# Speccy2007_128KY.net
KiCad netlist of a schematic drawn in EAGLE
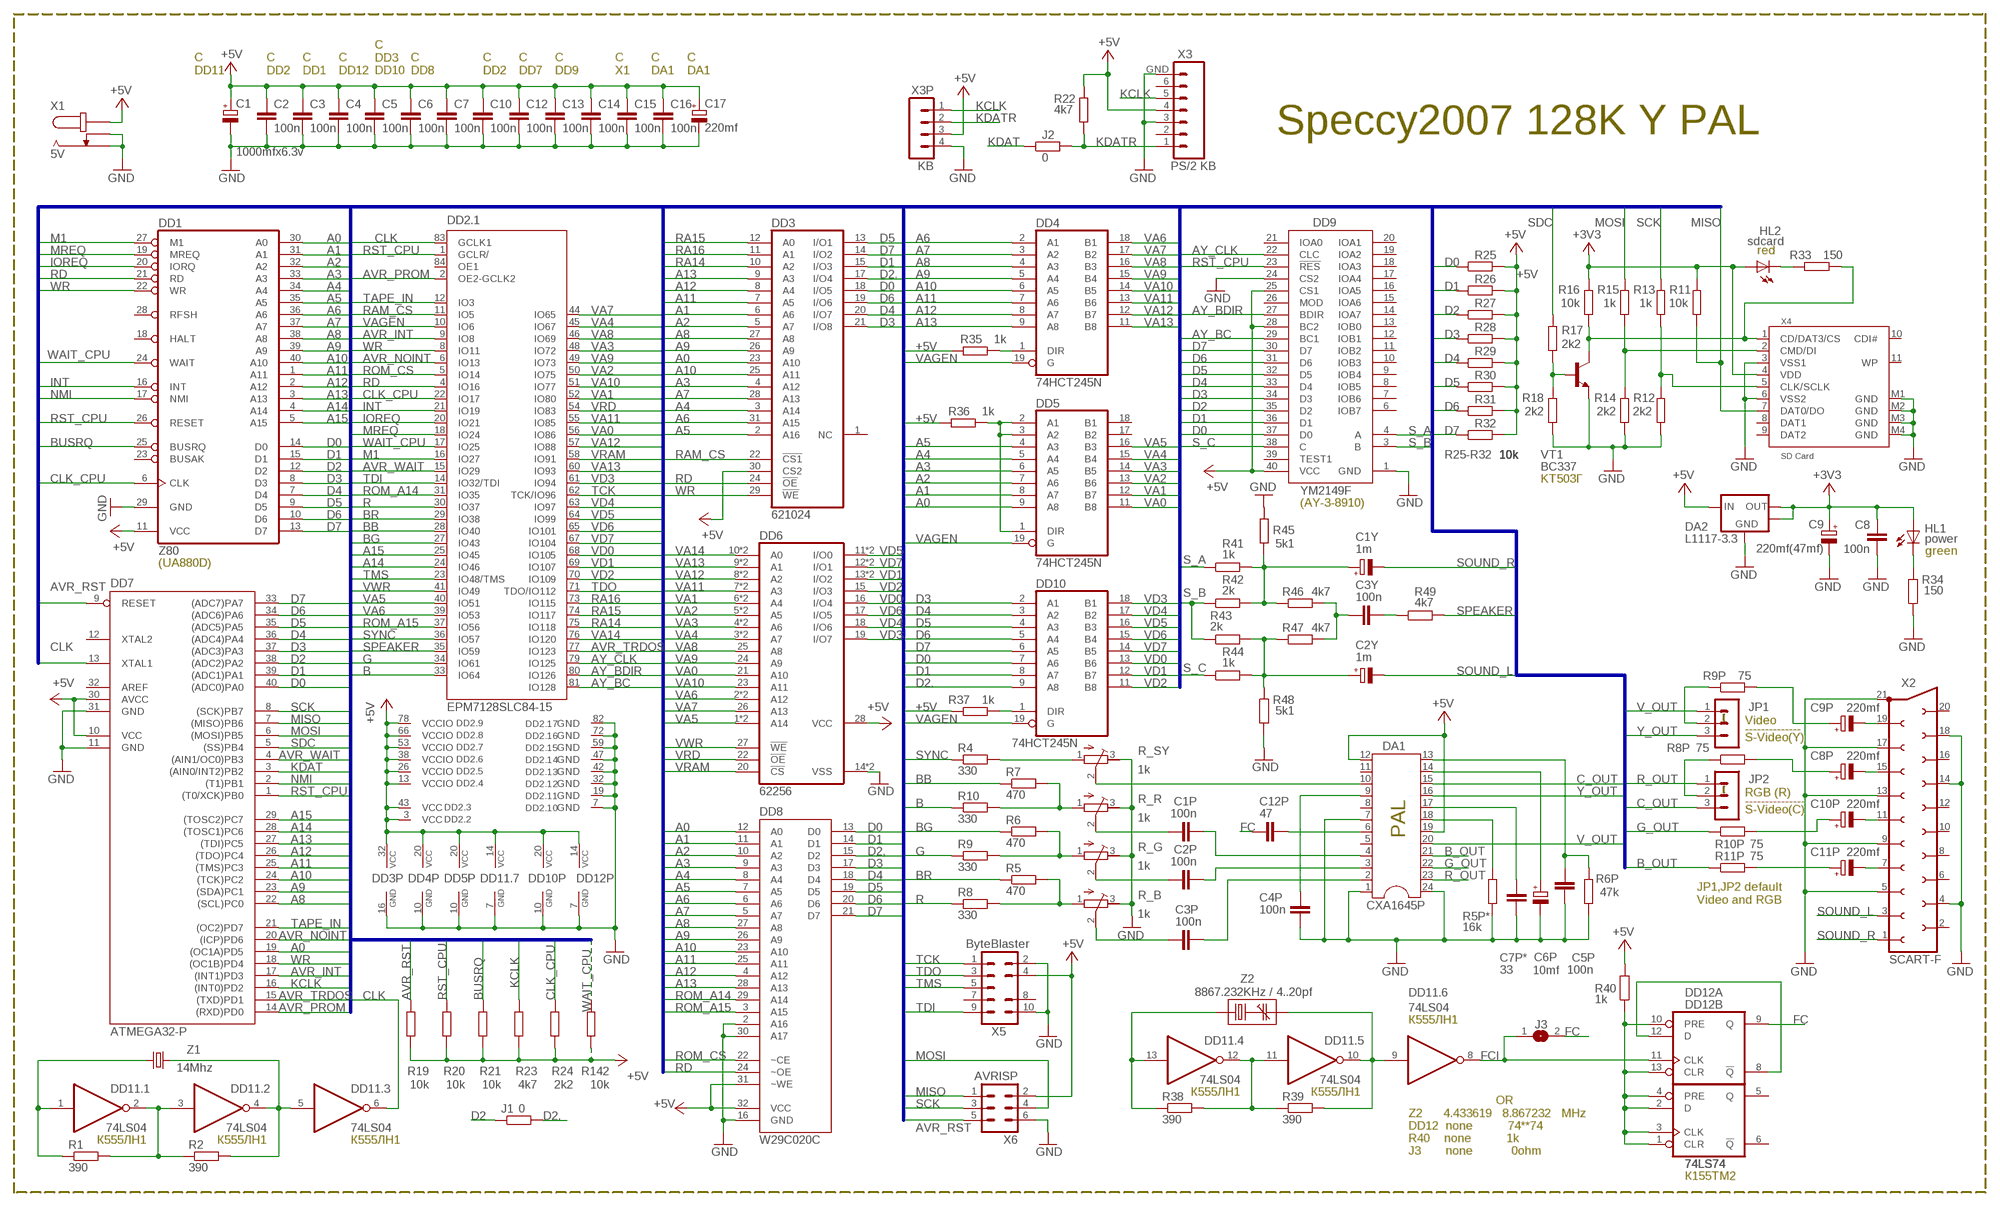
[diagram p0: schematic, sheet 1]

(export (version "E")
  (design (tool "Eeschema 10.0.6"))
  (components
    (comp (ref "C1")
      (value "1000mfx6.3v")
      (footprint "eagle-import:E3,5-8")
      (libsource (lib "eagle-import") (part "CPOL-EUE3.5-8"))
    )
    (comp (ref "C1P")
      (value "100n")
      (footprint "eagle-import:C0805")
      (libsource (lib "eagle-import") (part "C-EUC0805"))
    )
    (comp (ref "C1Y")
      (value "1m")
      (footprint "eagle-import:E2,5-5")
      (libsource (lib "eagle-import") (part "CPOL-EUE2.5-5"))
    )
    (comp (ref "C2")
      (value "100n")
      (footprint "eagle-import:C0805")
      (libsource (lib "eagle-import") (part "C-EUC0805"))
    )
    (comp (ref "C2P")
      (value "100n")
      (footprint "eagle-import:C0805")
      (libsource (lib "eagle-import") (part "C-EUC0805"))
    )
    (comp (ref "C2Y")
      (value "1m")
      (footprint "eagle-import:E2,5-5")
      (libsource (lib "eagle-import") (part "CPOL-EUE2.5-5"))
    )
    (comp (ref "C3")
      (value "100n")
      (footprint "eagle-import:C0805")
      (libsource (lib "eagle-import") (part "C-EUC0805"))
    )
    (comp (ref "C3P")
      (value "100n")
      (footprint "eagle-import:C0805")
      (libsource (lib "eagle-import") (part "C-EUC0805"))
    )
    (comp (ref "C3Y")
      (value "100n")
      (footprint "eagle-import:C0805")
      (libsource (lib "eagle-import") (part "C-EUC0805"))
    )
    (comp (ref "C4")
      (value "100n")
      (footprint "eagle-import:C1206")
      (libsource (lib "eagle-import") (part "C-EUC1206"))
    )
    (comp (ref "C4P")
      (value "100n")
      (footprint "eagle-import:C0805")
      (libsource (lib "eagle-import") (part "C-EUC0805"))
    )
    (comp (ref "C5")
      (value "100n")
      (footprint "eagle-import:C0805")
      (libsource (lib "eagle-import") (part "C-EUC0805"))
    )
    (comp (ref "C5P")
      (value "100n")
      (footprint "eagle-import:C1206")
      (libsource (lib "eagle-import") (part "C-EUC1206"))
    )
    (comp (ref "C6")
      (value "100n")
      (footprint "eagle-import:C1206")
      (libsource (lib "eagle-import") (part "C-EUC1206"))
    )
    (comp (ref "C6P")
      (value "10mf")
      (footprint "eagle-import:E2,5-5")
      (libsource (lib "eagle-import") (part "CPOL-EUE2.5-5"))
    )
    (comp (ref "C7")
      (value "100n")
      (footprint "eagle-import:C0805")
      (libsource (lib "eagle-import") (part "C-EUC0805"))
    )
    (comp (ref "C7P*")
      (value "33")
      (footprint "eagle-import:C1206")
      (libsource (lib "eagle-import") (part "C-EUC1206"))
    )
    (comp (ref "C8")
      (value "100n")
      (footprint "eagle-import:C0805")
      (libsource (lib "eagle-import") (part "C-EUC0805"))
    )
    (comp (ref "C8P")
      (value "220mf")
      (footprint "eagle-import:E2,5-6")
      (libsource (lib "eagle-import") (part "CPOL-EUE2.5-6"))
    )
    (comp (ref "C9")
      (value "220mf(47mf)")
      (footprint "eagle-import:E2,5-6")
      (libsource (lib "eagle-import") (part "CPOL-EUE2.5-6"))
    )
    (comp (ref "C9P")
      (value "220mf")
      (footprint "eagle-import:E2,5-6")
      (libsource (lib "eagle-import") (part "CPOL-EUE2.5-6"))
    )
    (comp (ref "C10")
      (value "100n")
      (footprint "eagle-import:C0805")
      (libsource (lib "eagle-import") (part "C-EUC0805"))
    )
    (comp (ref "C10P")
      (value "220mf")
      (footprint "eagle-import:E2,5-6")
      (libsource (lib "eagle-import") (part "CPOL-EUE2.5-6"))
    )
    (comp (ref "C11P")
      (value "220mf")
      (footprint "eagle-import:E2,5-6")
      (libsource (lib "eagle-import") (part "CPOL-EUE2.5-6"))
    )
    (comp (ref "C12")
      (value "100n")
      (footprint "eagle-import:C0805")
      (libsource (lib "eagle-import") (part "C-EUC0805"))
    )
    (comp (ref "C12P")
      (value "47")
      (footprint "eagle-import:C0805")
      (libsource (lib "eagle-import") (part "C-EUC0805"))
    )
    (comp (ref "C13")
      (value "100n")
      (footprint "eagle-import:C0805")
      (libsource (lib "eagle-import") (part "C-EUC0805"))
    )
    (comp (ref "C14")
      (value "100n")
      (footprint "eagle-import:C0805")
      (libsource (lib "eagle-import") (part "C-EUC0805"))
    )
    (comp (ref "C15")
      (value "100n")
      (footprint "eagle-import:C0805")
      (libsource (lib "eagle-import") (part "C-EUC0805"))
    )
    (comp (ref "C16")
      (value "100n")
      (footprint "eagle-import:C0805")
      (libsource (lib "eagle-import") (part "C-EUC0805"))
    )
    (comp (ref "C17")
      (value "220mf")
      (footprint "eagle-import:E2,5-6")
      (libsource (lib "eagle-import") (part "CPOL-EUE2.5-6"))
    )
    (comp (ref "DA1")
      (value "CXA1645P")
      (footprint "eagle-import:DIL24-4")
      (libsource (lib "eagle-import") (part "CXA1645-P"))
    )
    (comp (ref "DA2")
      (value "L1117-3.3")
      (footprint "eagle-import:SOT-223")
      (libsource (lib "eagle-import") (part "AP1117"))
    )
    (comp (ref "DD1")
      (value "Z80")
      (footprint "eagle-import:DIL40")
      (libsource (lib "eagle-import") (part "Z80CPU"))
    )
    (comp (ref "DD2")
      (value "EPM7128SLC84-15")
      (footprint "eagle-import:PGA-84-B")
      (libsource (lib "eagle-import") (part "EPM7128-J84"))
    )
    (comp (ref "DD3")
      (value "621024")
      (footprint "eagle-import:DIL32")
      (libsource (lib "eagle-import") (part "621024P"))
    )
    (comp (ref "DD4")
      (value "74HCT245N")
      (footprint "eagle-import:DIL20")
      (libsource (lib "eagle-import") (part "74245NHC"))
    )
    (comp (ref "DD5")
      (value "74HCT245N")
      (footprint "eagle-import:DIL20")
      (libsource (lib "eagle-import") (part "74245NHC"))
    )
    (comp (ref "DD6")
      (value "62256")
      (footprint "eagle-import:DIL28+6")
      (libsource (lib "eagle-import") (part "62256P+"))
    )
    (comp (ref "DD7")
      (value "ATMEGA32-P")
      (footprint "eagle-import:DIL40")
      (fields (field (name "MPN") "ATMEGA16-16PU"))
      (libsource (lib "eagle-import") (part "MEGA16-P"))
    )
    (comp (ref "DD8")
      (value "W29C020C")
      (footprint "eagle-import:DIL32")
      (libsource (lib "eagle-import") (part "W29C020C"))
    )
    (comp (ref "DD9")
      (value "YM2149F")
      (footprint "eagle-import:DIL40")
      (libsource (lib "eagle-import") (part "YM2149F"))
    )
    (comp (ref "DD10")
      (value "74HCT245N")
      (footprint "eagle-import:DIL20")
      (libsource (lib "eagle-import") (part "74245NHC"))
    )
    (comp (ref "DD11")
      (value "74LS04")
      (footprint "eagle-import:DIL14")
      (libsource (lib "eagle-import") (part "7404NLS"))
    )
    (comp (ref "DD12")
      (value "74LS74")
      (footprint "eagle-import:DIL14O")
      (libsource (lib "eagle-import") (part "7474OLS"))
    )
    (comp (ref "HL1")
      (value "power")
      (footprint "eagle-import:SML0805")
      (libsource (lib "eagle-import") (part "LEDSML0805"))
    )
    (comp (ref "HL2")
      (value "sdcard")
      (footprint "eagle-import:SML0805")
      (libsource (lib "eagle-import") (part "LEDSML0805"))
    )
    (comp (ref "J1")
      (value "0")
      (footprint "eagle-import:M1206")
      (libsource (lib "eagle-import") (part "rcl_R-EU_M1206"))
    )
    (comp (ref "J2")
      (value "0")
      (footprint "eagle-import:R1206")
      (libsource (lib "eagle-import") (part "rcl_R-EU_R1206"))
    )
    (comp (ref "J3") (value "SJ") (footprint "eagle-import:SJ") (libsource (lib "eagle-import") (part "SJ")))
    (comp (ref "JP1")
      (value "MA03-1")
      (footprint "eagle-import:MA03-1")
      (libsource (lib "eagle-import") (part "MA03-1"))
    )
    (comp (ref "JP2")
      (value "MA03-1")
      (footprint "eagle-import:MA03-1")
      (fields (field (name "OC_FARNELL") "unknown") (field (name "OC_NEWARK") "unknown"))
      (libsource (lib "eagle-import") (part "MA03-1"))
    )
    (comp (ref "R1")
      (value "390")
      (footprint "eagle-import:R0805")
      (libsource (lib "eagle-import") (part "rcl_R-EU_R0805"))
    )
    (comp (ref "R2")
      (value "390")
      (footprint "eagle-import:R0805")
      (libsource (lib "eagle-import") (part "rcl_R-EU_R0805"))
    )
    (comp (ref "R4")
      (value "330")
      (footprint "eagle-import:R0805")
      (libsource (lib "eagle-import") (part "rcl_R-EU_R0805"))
    )
    (comp (ref "R5")
      (value "470")
      (footprint "eagle-import:R0805")
      (libsource (lib "eagle-import") (part "rcl_R-EU_R0805"))
    )
    (comp (ref "R5P*")
      (value "16k")
      (footprint "eagle-import:M1206")
      (libsource (lib "eagle-import") (part "rcl_R-EU_M1206"))
    )
    (comp (ref "R6")
      (value "470")
      (footprint "eagle-import:R1206")
      (libsource (lib "eagle-import") (part "rcl_R-EU_R1206"))
    )
    (comp (ref "R6P")
      (value "47k")
      (footprint "eagle-import:R0805")
      (libsource (lib "eagle-import") (part "rcl_R-EU_R0805"))
    )
    (comp (ref "R7")
      (value "470")
      (footprint "eagle-import:0207_10")
      (libsource (lib "eagle-import") (part "R-EU_0207/10"))
    )
    (comp (ref "R8")
      (value "330")
      (footprint "eagle-import:R0805")
      (libsource (lib "eagle-import") (part "rcl_R-EU_R0805"))
    )
    (comp (ref "R8P")
      (value "75")
      (footprint "eagle-import:R1206")
      (libsource (lib "eagle-import") (part "rcl_R-EU_R1206"))
    )
    (comp (ref "R9")
      (value "330")
      (footprint "eagle-import:R0805")
      (libsource (lib "eagle-import") (part "rcl_R-EU_R0805"))
    )
    (comp (ref "R9P")
      (value "75")
      (footprint "eagle-import:R1206")
      (libsource (lib "eagle-import") (part "rcl_R-EU_R1206"))
    )
    (comp (ref "R10")
      (value "330")
      (footprint "eagle-import:R0805")
      (libsource (lib "eagle-import") (part "rcl_R-EU_R0805"))
    )
    (comp (ref "R10P")
      (value "75")
      (footprint "eagle-import:R1206")
      (libsource (lib "eagle-import") (part "rcl_R-EU_R1206"))
    )
    (comp (ref "R11")
      (value "10k")
      (footprint "eagle-import:R0805")
      (libsource (lib "eagle-import") (part "rcl_R-EU_R0805"))
    )
    (comp (ref "R11P")
      (value "75")
      (footprint "eagle-import:R1206")
      (libsource (lib "eagle-import") (part "rcl_R-EU_R1206"))
    )
    (comp (ref "R12")
      (value "2k2")
      (footprint "eagle-import:R1206")
      (libsource (lib "eagle-import") (part "rcl_R-EU_R1206"))
    )
    (comp (ref "R13")
      (value "1k")
      (footprint "eagle-import:R0805")
      (libsource (lib "eagle-import") (part "rcl_R-EU_R0805"))
    )
    (comp (ref "R14")
      (value "2k2")
      (footprint "eagle-import:R0805")
      (libsource (lib "eagle-import") (part "rcl_R-EU_R0805"))
    )
    (comp (ref "R15")
      (value "1k")
      (footprint "eagle-import:R0805")
      (libsource (lib "eagle-import") (part "rcl_R-EU_R0805"))
    )
    (comp (ref "R16")
      (value "10k")
      (footprint "eagle-import:R0805")
      (libsource (lib "eagle-import") (part "rcl_R-EU_R0805"))
    )
    (comp (ref "R17")
      (value "2k2")
      (footprint "eagle-import:R0805")
      (libsource (lib "eagle-import") (part "rcl_R-EU_R0805"))
    )
    (comp (ref "R18")
      (value "2k2")
      (footprint "eagle-import:R0805")
      (libsource (lib "eagle-import") (part "rcl_R-EU_R0805"))
    )
    (comp (ref "R19")
      (value "10k")
      (footprint "eagle-import:M0805")
      (libsource (lib "eagle-import") (part "rcl_R-EU_M0805"))
    )
    (comp (ref "R20")
      (value "10k")
      (footprint "eagle-import:R0805")
      (libsource (lib "eagle-import") (part "rcl_R-EU_R0805"))
    )
    (comp (ref "R21")
      (value "10k")
      (footprint "eagle-import:0207_10")
      (libsource (lib "eagle-import") (part "R-EU_0207/10"))
    )
    (comp (ref "R22")
      (value "4k7")
      (footprint "eagle-import:R0805")
      (libsource (lib "eagle-import") (part "rcl_R-EU_R0805"))
    )
    (comp (ref "R23")
      (value "4k7")
      (footprint "eagle-import:R1206")
      (libsource (lib "eagle-import") (part "rcl_R-EU_R1206"))
    )
    (comp (ref "R24")
      (value "2k2")
      (footprint "eagle-import:0207_10")
      (libsource (lib "eagle-import") (part "R-EU_0207/10"))
    )
    (comp (ref "R25")
      (value "10k")
      (footprint "eagle-import:R0805")
      (libsource (lib "eagle-import") (part "rcl_R-EU_R0805"))
    )
    (comp (ref "R26")
      (value "10k")
      (footprint "eagle-import:M0805")
      (libsource (lib "eagle-import") (part "rcl_R-EU_M0805"))
    )
    (comp (ref "R27")
      (value "10k")
      (footprint "eagle-import:R0805")
      (libsource (lib "eagle-import") (part "rcl_R-EU_R0805"))
    )
    (comp (ref "R28")
      (value "10k")
      (footprint "eagle-import:R0805")
      (libsource (lib "eagle-import") (part "rcl_R-EU_R0805"))
    )
    (comp (ref "R29")
      (value "10k")
      (footprint "eagle-import:R0805")
      (libsource (lib "eagle-import") (part "rcl_R-EU_R0805"))
    )
    (comp (ref "R30")
      (value "10k")
      (footprint "eagle-import:R0805")
      (libsource (lib "eagle-import") (part "rcl_R-EU_R0805"))
    )
    (comp (ref "R31")
      (value "10k")
      (footprint "eagle-import:R0805")
      (libsource (lib "eagle-import") (part "rcl_R-EU_R0805"))
    )
    (comp (ref "R32")
      (value "10k")
      (footprint "eagle-import:R0805")
      (libsource (lib "eagle-import") (part "rcl_R-EU_R0805"))
    )
    (comp (ref "R33")
      (value "150")
      (footprint "eagle-import:R1206")
      (libsource (lib "eagle-import") (part "rcl_R-EU_R1206"))
    )
    (comp (ref "R34")
      (value "150")
      (footprint "eagle-import:R0805")
      (libsource (lib "eagle-import") (part "rcl_R-EU_R0805"))
    )
    (comp (ref "R35")
      (value "1k")
      (footprint "eagle-import:R0805")
      (libsource (lib "eagle-import") (part "rcl_R-EU_R0805"))
    )
    (comp (ref "R36")
      (value "1k")
      (footprint "eagle-import:R0805")
      (libsource (lib "eagle-import") (part "rcl_R-EU_R0805"))
    )
    (comp (ref "R37")
      (value "1k")
      (footprint "eagle-import:R0805")
      (libsource (lib "eagle-import") (part "rcl_R-EU_R0805"))
    )
    (comp (ref "R38")
      (value "390")
      (footprint "eagle-import:R0805")
      (libsource (lib "eagle-import") (part "rcl_R-EU_R0805"))
    )
    (comp (ref "R39")
      (value "390")
      (footprint "eagle-import:R0805")
      (libsource (lib "eagle-import") (part "rcl_R-EU_R0805"))
    )
    (comp (ref "R40")
      (value "1k")
      (footprint "eagle-import:R0805")
      (libsource (lib "eagle-import") (part "rcl_R-EU_R0805"))
    )
    (comp (ref "R41")
      (value "1k")
      (footprint "eagle-import:R0805")
      (libsource (lib "eagle-import") (part "rcl_R-EU_R0805"))
    )
    (comp (ref "R42")
      (value "2k")
      (footprint "eagle-import:R0805")
      (libsource (lib "eagle-import") (part "rcl_R-EU_R0805"))
    )
    (comp (ref "R43")
      (value "2k")
      (footprint "eagle-import:R0805")
      (libsource (lib "eagle-import") (part "rcl_R-EU_R0805"))
    )
    (comp (ref "R44")
      (value "1k")
      (footprint "eagle-import:R1206")
      (libsource (lib "eagle-import") (part "rcl_R-EU_R1206"))
    )
    (comp (ref "R45")
      (value "5k1")
      (footprint "eagle-import:R1206")
      (libsource (lib "eagle-import") (part "rcl_R-EU_R1206"))
    )
    (comp (ref "R46")
      (value "4k7")
      (footprint "eagle-import:R1206")
      (libsource (lib "eagle-import") (part "rcl_R-EU_R1206"))
    )
    (comp (ref "R47")
      (value "4k7")
      (footprint "eagle-import:R0805")
      (libsource (lib "eagle-import") (part "rcl_R-EU_R0805"))
    )
    (comp (ref "R48")
      (value "5k1")
      (footprint "eagle-import:R0805")
      (libsource (lib "eagle-import") (part "rcl_R-EU_R0805"))
    )
    (comp (ref "R49")
      (value "4k7")
      (footprint "eagle-import:R0805")
      (libsource (lib "eagle-import") (part "rcl_R-EU_R0805"))
    )
    (comp (ref "R142")
      (value "10k")
      (footprint "eagle-import:0207_10")
      (libsource (lib "eagle-import") (part "R-EU_0207/10"))
    )
    (comp (ref "R_B")
      (value "1k")
      (footprint "eagle-import:RTRIM3296W")
      (libsource (lib "eagle-import") (part "R-TRIMM3296W"))
    )
    (comp (ref "R_G")
      (value "1k")
      (footprint "eagle-import:RTRIM3296W")
      (libsource (lib "eagle-import") (part "R-TRIMM3296W"))
    )
    (comp (ref "R_R")
      (value "1k")
      (footprint "eagle-import:RTRIM3296W")
      (libsource (lib "eagle-import") (part "R-TRIMM3296W"))
    )
    (comp (ref "R_SY")
      (value "1k")
      (footprint "eagle-import:RTRIM3296W")
      (libsource (lib "eagle-import") (part "R-TRIMM3296W"))
    )
    (comp (ref "VT1")
      (value "BC337")
      (footprint "eagle-import:TO92-CBE")
      (libsource (lib "eagle-import") (part "-NPN-TO92-CBEBC550"))
    )
    (comp (ref "X1")
      (value "5V")
      (footprint "eagle-import:POWER3.5")
      (libsource (lib "eagle-import") (part "POWER3.5"))
    )
    (comp (ref "X2")
      (value "SCART-F")
      (footprint "eagle-import:SCART-F")
      (libsource (lib "eagle-import") (part "SCART-F"))
    )
    (comp (ref "X3")
      (value "PS/2 KB")
      (footprint "eagle-import:MINI-DIN6")
      (libsource (lib "eagle-import") (part "MINI-DIN6PTH"))
    )
    (comp (ref "X3P")
      (value "KB")
      (footprint "eagle-import:MA04-1")
      (libsource (lib "eagle-import") (part "MA04-1"))
    )
    (comp (ref "X4")
      (value "SD Card")
      (footprint "eagle-import:SDCMF-10915W010")
      (libsource (lib "eagle-import") (part "SDCARD"))
    )
    (comp (ref "X5")
      (value "ByteBlaster")
      (footprint "eagle-import:MA05-2")
      (libsource (lib "eagle-import") (part "MA05-2"))
    )
    (comp (ref "X6")
      (value "AVRISP")
      (footprint "eagle-import:MA03-2")
      (libsource (lib "eagle-import") (part "MA03-2"))
    )
    (comp (ref "Z1")
      (value "14Mhz")
      (footprint "eagle-import:HC49U-H")
      (libsource (lib "eagle-import") (part "CRYSTALHC49U-H"))
    )
    (comp (ref "Z2")
      (value "8867.232KHz / 4..20pf")
      (footprint "eagle-import:HC49U-H")
      (libsource (lib "eagle-import") (part "ZC"))
    )
  )
  (nets
    (net (code "1") (name "+3V3") (class "Default")
      (node (ref "C8") (pin "1") (pinfunction "1_1") (pintype "passive"))
      (node (ref "C9") (pin "+") (pinfunction "+_+") (pintype "passive"))
      (node (ref "DA2") (pin "2") (pinfunction "OUT_2") (pintype "power_in"))
      (node (ref "DA2") (pin "4") (pinfunction "OUT'_4") (pintype "power_in"))
      (node (ref "HL1") (pin "A") (pinfunction "A_A") (pintype "passive"))
      (node (ref "HL2") (pin "A") (pinfunction "A_A") (pintype "passive"))
      (node (ref "R11") (pin "2") (pinfunction "2_2") (pintype "passive"))
      (node (ref "R16") (pin "2") (pinfunction "2_2") (pintype "passive"))
      (node (ref "X4") (pin "4") (pinfunction "VDD_4") (pintype "power_in"))
    )
    (net (code "2") (name "+5V") (class "Default")
      (node (ref "C1") (pin "+") (pinfunction "+_+") (pintype "passive"))
      (node (ref "C10") (pin "1") (pinfunction "1_1") (pintype "passive"))
      (node (ref "C12") (pin "1") (pinfunction "1_1") (pintype "passive"))
      (node (ref "C13") (pin "1") (pinfunction "1_1") (pintype "passive"))
      (node (ref "C14") (pin "1") (pinfunction "1_1") (pintype "passive"))
      (node (ref "C15") (pin "1") (pinfunction "1_1") (pintype "passive"))
      (node (ref "C16") (pin "1") (pinfunction "1_1") (pintype "passive"))
      (node (ref "C17") (pin "+") (pinfunction "+_+") (pintype "passive"))
      (node (ref "C2") (pin "1") (pinfunction "1_1") (pintype "passive"))
      (node (ref "C3") (pin "1") (pinfunction "1_1") (pintype "passive"))
      (node (ref "C4") (pin "1") (pinfunction "1_1") (pintype "passive"))
      (node (ref "C5") (pin "1") (pinfunction "1_1") (pintype "passive"))
      (node (ref "C6") (pin "1") (pinfunction "1_1") (pintype "passive"))
      (node (ref "C7") (pin "1") (pinfunction "1_1") (pintype "passive"))
      (node (ref "DA1") (pin "12") (pinfunction "12_12") (pintype "passive"))
      (node (ref "DA1") (pin "19") (pinfunction "19_19") (pintype "passive"))
      (node (ref "DA2") (pin "3") (pinfunction "IN_3") (pintype "power_in"))
      (node (ref "DD1") (pin "11") (pinfunction "VCC_11") (pintype "power_in"))
      (node (ref "DD10") (pin "20") (pinfunction "VCC_20") (pintype "power_in"))
      (node (ref "DD11") (pin "14") (pinfunction "VCC_14") (pintype "power_in"))
      (node (ref "DD12") (pin "14") (pinfunction "VCC_14") (pintype "power_in"))
      (node (ref "DD2") (pin "13") (pinfunction "VCCIO_13") (pintype "power_in"))
      (node (ref "DD2") (pin "26") (pinfunction "VCCIO_26") (pintype "power_in"))
      (node (ref "DD2") (pin "3") (pinfunction "VCC_3") (pintype "power_in"))
      (node (ref "DD2") (pin "38") (pinfunction "VCCIO_38") (pintype "power_in"))
      (node (ref "DD2") (pin "43") (pinfunction "VCC_43") (pintype "power_in"))
      (node (ref "DD2") (pin "53") (pinfunction "VCCIO_53") (pintype "power_in"))
      (node (ref "DD2") (pin "66") (pinfunction "VCCIO_66") (pintype "power_in"))
      (node (ref "DD2") (pin "78") (pinfunction "VCCIO_78") (pintype "power_in"))
      (node (ref "DD3") (pin "30") (pinfunction "CS2_30") (pintype "input"))
      (node (ref "DD3") (pin "32") (pinfunction "VCC_32") (pintype "power_in"))
      (node (ref "DD4") (pin "20") (pinfunction "VCC_20") (pintype "power_in"))
      (node (ref "DD5") (pin "20") (pinfunction "VCC_20") (pintype "power_in"))
      (node (ref "DD6") (pin "28") (pinfunction "VCC_28") (pintype "power_in"))
      (node (ref "DD7") (pin "10") (pinfunction "VCC_10") (pintype "power_in"))
      (node (ref "DD7") (pin "30") (pinfunction "AVCC_30") (pintype "power_in"))
      (node (ref "DD8") (pin "31") (pinfunction "~{WE}_31") (pintype "input"))
      (node (ref "DD8") (pin "32") (pinfunction "VCC_32") (pintype "power_in"))
      (node (ref "DD9") (pin "25") (pinfunction "CS1_25") (pintype "bidirectional"))
      (node (ref "DD9") (pin "28") (pinfunction "BC2_28") (pintype "bidirectional"))
      (node (ref "DD9") (pin "40") (pinfunction "VCC_40") (pintype "bidirectional"))
      (node (ref "R142") (pin "1") (pinfunction "1_1") (pintype "passive"))
      (node (ref "R19") (pin "1") (pinfunction "1_1") (pintype "passive"))
      (node (ref "R20") (pin "1") (pinfunction "1_1") (pintype "passive"))
      (node (ref "R21") (pin "1") (pinfunction "1_1") (pintype "passive"))
      (node (ref "R22") (pin "2") (pinfunction "2_2") (pintype "passive"))
      (node (ref "R23") (pin "1") (pinfunction "1_1") (pintype "passive"))
      (node (ref "R24") (pin "1") (pinfunction "1_1") (pintype "passive"))
      (node (ref "R25") (pin "2") (pinfunction "2_2") (pintype "passive"))
      (node (ref "R26") (pin "2") (pinfunction "2_2") (pintype "passive"))
      (node (ref "R27") (pin "2") (pinfunction "2_2") (pintype "passive"))
      (node (ref "R28") (pin "2") (pinfunction "2_2") (pintype "passive"))
      (node (ref "R29") (pin "2") (pinfunction "2_2") (pintype "passive"))
      (node (ref "R30") (pin "2") (pinfunction "2_2") (pintype "passive"))
      (node (ref "R31") (pin "2") (pinfunction "2_2") (pintype "passive"))
      (node (ref "R32") (pin "2") (pinfunction "2_2") (pintype "passive"))
      (node (ref "R35") (pin "2") (pinfunction "2_2") (pintype "passive"))
      (node (ref "R36") (pin "2") (pinfunction "2_2") (pintype "passive"))
      (node (ref "R37") (pin "2") (pinfunction "2_2") (pintype "passive"))
      (node (ref "R40") (pin "2") (pinfunction "2_2") (pintype "passive"))
      (node (ref "X1") (pin "P$1") (pinfunction "1_P$1") (pintype "passive"))
      (node (ref "X3") (pin "4") (pinfunction "4_4") (pintype "passive"))
      (node (ref "X3P") (pin "3") (pinfunction "3_3") (pintype "passive"))
      (node (ref "X5") (pin "4") (pinfunction "4_4") (pintype "passive"))
      (node (ref "X6") (pin "2") (pinfunction "2_2") (pintype "passive"))
    )
    (net (code "3") (name "/A0") (class "Default")
      (node (ref "DD1") (pin "30") (pinfunction "A0_30") (pintype "output"))
      (node (ref "DD3") (pin "23") (pinfunction "A10_23") (pintype "input"))
      (node (ref "DD5") (pin "9") (pinfunction "A8_9") (pintype "bidirectional"))
      (node (ref "DD7") (pin "19") (pinfunction "(OC1A)PD5_19") (pintype "bidirectional"))
      (node (ref "DD8") (pin "12") (pinfunction "A0_12") (pintype "input"))
    )
    (net (code "4") (name "/A1") (class "Default")
      (node (ref "DD1") (pin "31") (pinfunction "A1_31") (pintype "output"))
      (node (ref "DD3") (pin "6") (pinfunction "A6_6") (pintype "input"))
      (node (ref "DD5") (pin "8") (pinfunction "A7_8") (pintype "bidirectional"))
      (node (ref "DD8") (pin "11") (pinfunction "A1_11") (pintype "input"))
    )
    (net (code "5") (name "/A2") (class "Default")
      (node (ref "DD1") (pin "32") (pinfunction "A2_32") (pintype "output"))
      (node (ref "DD3") (pin "5") (pinfunction "A7_5") (pintype "input"))
      (node (ref "DD5") (pin "7") (pinfunction "A6_7") (pintype "bidirectional"))
      (node (ref "DD8") (pin "10") (pinfunction "A2_10") (pintype "input"))
    )
    (net (code "6") (name "/A3") (class "Default")
      (node (ref "DD1") (pin "33") (pinfunction "A3_33") (pintype "output"))
      (node (ref "DD3") (pin "4") (pinfunction "A12_4") (pintype "input"))
      (node (ref "DD5") (pin "6") (pinfunction "A5_6") (pintype "bidirectional"))
      (node (ref "DD8") (pin "9") (pinfunction "A3_9") (pintype "input"))
    )
    (net (code "7") (name "/A4") (class "Default")
      (node (ref "DD1") (pin "34") (pinfunction "A4_34") (pintype "output"))
      (node (ref "DD3") (pin "3") (pinfunction "A14_3") (pintype "input"))
      (node (ref "DD5") (pin "5") (pinfunction "A4_5") (pintype "bidirectional"))
      (node (ref "DD8") (pin "8") (pinfunction "A4_8") (pintype "input"))
    )
    (net (code "8") (name "/A5") (class "Default")
      (node (ref "DD1") (pin "35") (pinfunction "A5_35") (pintype "output"))
      (node (ref "DD3") (pin "2") (pinfunction "A16_2") (pintype "input"))
      (node (ref "DD5") (pin "4") (pinfunction "A3_4") (pintype "bidirectional"))
      (node (ref "DD8") (pin "7") (pinfunction "A5_7") (pintype "input"))
    )
    (net (code "9") (name "/A6") (class "Default")
      (node (ref "DD1") (pin "36") (pinfunction "A6_36") (pintype "output"))
      (node (ref "DD3") (pin "31") (pinfunction "A15_31") (pintype "input"))
      (node (ref "DD4") (pin "2") (pinfunction "A1_2") (pintype "bidirectional"))
      (node (ref "DD8") (pin "6") (pinfunction "A6_6") (pintype "input"))
    )
    (net (code "10") (name "/A7") (class "Default")
      (node (ref "DD1") (pin "37") (pinfunction "A7_37") (pintype "output"))
      (node (ref "DD3") (pin "28") (pinfunction "A13_28") (pintype "input"))
      (node (ref "DD4") (pin "3") (pinfunction "A2_3") (pintype "bidirectional"))
      (node (ref "DD8") (pin "5") (pinfunction "A7_5") (pintype "input"))
    )
    (net (code "11") (name "/A8") (class "Default")
      (node (ref "DD1") (pin "38") (pinfunction "A8_38") (pintype "output"))
      (node (ref "DD3") (pin "27") (pinfunction "A8_27") (pintype "input"))
      (node (ref "DD4") (pin "4") (pinfunction "A3_4") (pintype "bidirectional"))
      (node (ref "DD7") (pin "22") (pinfunction "(SCL)PC0_22") (pintype "bidirectional"))
      (node (ref "DD8") (pin "27") (pinfunction "A8_27") (pintype "input"))
    )
    (net (code "12") (name "/A9") (class "Default")
      (node (ref "DD1") (pin "39") (pinfunction "A9_39") (pintype "output"))
      (node (ref "DD3") (pin "26") (pinfunction "A9_26") (pintype "input"))
      (node (ref "DD4") (pin "5") (pinfunction "A4_5") (pintype "bidirectional"))
      (node (ref "DD7") (pin "23") (pinfunction "(SDA)PC1_23") (pintype "bidirectional"))
      (node (ref "DD8") (pin "26") (pinfunction "A9_26") (pintype "input"))
    )
    (net (code "13") (name "/A10") (class "Default")
      (node (ref "DD1") (pin "40") (pinfunction "A10_40") (pintype "output"))
      (node (ref "DD3") (pin "25") (pinfunction "A11_25") (pintype "input"))
      (node (ref "DD4") (pin "6") (pinfunction "A5_6") (pintype "bidirectional"))
      (node (ref "DD7") (pin "24") (pinfunction "(TCK)PC2_24") (pintype "bidirectional"))
      (node (ref "DD8") (pin "23") (pinfunction "A10_23") (pintype "input"))
    )
    (net (code "14") (name "/A11") (class "Default")
      (node (ref "DD1") (pin "1") (pinfunction "A11_1") (pintype "output"))
      (node (ref "DD3") (pin "7") (pinfunction "A5_7") (pintype "input"))
      (node (ref "DD4") (pin "7") (pinfunction "A6_7") (pintype "bidirectional"))
      (node (ref "DD7") (pin "25") (pinfunction "(TMS)PC3_25") (pintype "bidirectional"))
      (node (ref "DD8") (pin "25") (pinfunction "A11_25") (pintype "input"))
    )
    (net (code "15") (name "/A12") (class "Default")
      (node (ref "DD1") (pin "2") (pinfunction "A12_2") (pintype "output"))
      (node (ref "DD3") (pin "8") (pinfunction "A4_8") (pintype "input"))
      (node (ref "DD4") (pin "8") (pinfunction "A7_8") (pintype "bidirectional"))
      (node (ref "DD7") (pin "26") (pinfunction "(TDO)PC4_26") (pintype "bidirectional"))
      (node (ref "DD8") (pin "4") (pinfunction "A12_4") (pintype "input"))
    )
    (net (code "16") (name "/A13") (class "Default")
      (node (ref "DD1") (pin "3") (pinfunction "A13_3") (pintype "output"))
      (node (ref "DD3") (pin "9") (pinfunction "A3_9") (pintype "input"))
      (node (ref "DD4") (pin "9") (pinfunction "A8_9") (pintype "bidirectional"))
      (node (ref "DD7") (pin "27") (pinfunction "(TDI)PC5_27") (pintype "bidirectional"))
      (node (ref "DD8") (pin "28") (pinfunction "A13_28") (pintype "input"))
    )
    (net (code "17") (name "/A14") (class "Default")
      (node (ref "DD1") (pin "4") (pinfunction "A14_4") (pintype "output"))
      (node (ref "DD2") (pin "24") (pinfunction "IO46_24") (pintype "bidirectional"))
      (node (ref "DD7") (pin "28") (pinfunction "(TOSC1)PC6_28") (pintype "bidirectional"))
    )
    (net (code "18") (name "/A15") (class "Default")
      (node (ref "DD1") (pin "5") (pinfunction "A15_5") (pintype "output"))
      (node (ref "DD2") (pin "25") (pinfunction "IO45_25") (pintype "bidirectional"))
      (node (ref "DD7") (pin "29") (pinfunction "(TOSC2)PC7_29") (pintype "bidirectional"))
    )
    (net (code "19") (name "/AVR_INT") (class "Default")
      (node (ref "DD2") (pin "9") (pinfunction "IO8_9") (pintype "bidirectional"))
      (node (ref "DD7") (pin "17") (pinfunction "(INT1)PD3_17") (pintype "bidirectional"))
    )
    (net (code "20") (name "/AVR_NOINT") (class "Default")
      (node (ref "DD2") (pin "6") (pinfunction "IO13_6") (pintype "bidirectional"))
      (node (ref "DD7") (pin "20") (pinfunction "(ICP)PD6_20") (pintype "bidirectional"))
    )
    (net (code "21") (name "/AVR_PROM") (class "Default")
      (node (ref "DD2") (pin "2") (pinfunction "OE2-GCLK2_2") (pintype "input"))
      (node (ref "DD7") (pin "14") (pinfunction "(RXD)PD0_14") (pintype "bidirectional"))
    )
    (net (code "22") (name "/AVR_RST") (class "Default")
      (node (ref "DD7") (pin "9") (pinfunction "RESET_9") (pintype "input"))
      (node (ref "R19") (pin "2") (pinfunction "2_2") (pintype "passive"))
      (node (ref "X6") (pin "5") (pinfunction "5_5") (pintype "passive"))
    )
    (net (code "23") (name "/AVR_TRDOS") (class "Default")
      (node (ref "DD2") (pin "77") (pinfunction "IO123_77") (pintype "bidirectional"))
      (node (ref "DD7") (pin "15") (pinfunction "(TXD)PD1_15") (pintype "bidirectional"))
    )
    (net (code "24") (name "/AVR_WAIT") (class "Default")
      (node (ref "DD2") (pin "15") (pinfunction "IO29_15") (pintype "bidirectional"))
      (node (ref "DD7") (pin "4") (pinfunction "(AIN1/OC0)PB3_4") (pintype "bidirectional"))
    )
    (net (code "25") (name "/AY_BC") (class "Default")
      (node (ref "DD2") (pin "81") (pinfunction "IO128_81") (pintype "bidirectional"))
      (node (ref "DD9") (pin "29") (pinfunction "BC1_29") (pintype "bidirectional"))
    )
    (net (code "26") (name "/AY_BDIR") (class "Default")
      (node (ref "DD2") (pin "80") (pinfunction "IO126_80") (pintype "bidirectional"))
      (node (ref "DD9") (pin "27") (pinfunction "BDIR_27") (pintype "bidirectional"))
    )
    (net (code "27") (name "/AY_CLK") (class "Default")
      (node (ref "DD2") (pin "79") (pinfunction "IO125_79") (pintype "bidirectional"))
      (node (ref "DD9") (pin "22") (pinfunction "CLC_22") (pintype "bidirectional"))
    )
    (net (code "28") (name "/B") (class "Default")
      (node (ref "DD2") (pin "33") (pinfunction "IO64_33") (pintype "bidirectional"))
      (node (ref "R10") (pin "1") (pinfunction "1_1") (pintype "passive"))
    )
    (net (code "29") (name "/BB") (class "Default")
      (node (ref "DD2") (pin "28") (pinfunction "IO40_28") (pintype "bidirectional"))
      (node (ref "R7") (pin "1") (pinfunction "1_1") (pintype "passive"))
    )
    (net (code "30") (name "/BG") (class "Default")
      (node (ref "DD2") (pin "27") (pinfunction "IO43_27") (pintype "bidirectional"))
      (node (ref "R6") (pin "1") (pinfunction "1_1") (pintype "passive"))
    )
    (net (code "31") (name "/BR") (class "Default")
      (node (ref "DD2") (pin "29") (pinfunction "IO38_29") (pintype "bidirectional"))
      (node (ref "R5") (pin "1") (pinfunction "1_1") (pintype "passive"))
    )
    (net (code "32") (name "/BUSRQ") (class "Default")
      (node (ref "DD1") (pin "25") (pinfunction "BUSRQ_25") (pintype "input"))
      (node (ref "R21") (pin "2") (pinfunction "2_2") (pintype "passive"))
    )
    (net (code "33") (name "/B_OUT") (class "Default")
      (node (ref "DA1") (pin "21") (pinfunction "21_21") (pintype "passive"))
      (node (ref "R11P") (pin "1") (pinfunction "1_1") (pintype "passive"))
    )
    (net (code "34") (name "/CLK") (class "Default")
      (node (ref "DD11") (pin "6") (pinfunction "O_6") (pintype "output"))
      (node (ref "DD2") (pin "83") (pinfunction "GCLK1_83") (pintype "input"))
      (node (ref "DD7") (pin "13") (pinfunction "XTAL1_13") (pintype "bidirectional"))
    )
    (net (code "35") (name "/CLK_CPU") (class "Default")
      (node (ref "DD1") (pin "6") (pinfunction "CLK_6") (pintype "input"))
      (node (ref "DD2") (pin "22") (pinfunction "IO17_22") (pintype "bidirectional"))
      (node (ref "R24") (pin "2") (pinfunction "2_2") (pintype "passive"))
    )
    (net (code "36") (name "/C_OUT") (class "Default")
      (node (ref "DA1") (pin "15") (pinfunction "15_15") (pintype "passive"))
      (node (ref "JP2") (pin "3") (pinfunction "3_3") (pintype "passive"))
    )
    (net (code "37") (name "/D0") (class "Default")
      (node (ref "DD1") (pin "14") (pinfunction "D0_14") (pintype "bidirectional"))
      (node (ref "DD10") (pin "7") (pinfunction "A6_7") (pintype "bidirectional"))
      (node (ref "DD3") (pin "18") (pinfunction "I/O5_18") (pintype "bidirectional"))
      (node (ref "DD7") (pin "40") (pinfunction "(ADC0)PA0_40") (pintype "bidirectional"))
      (node (ref "DD8") (pin "13") (pinfunction "D0_13") (pintype "bidirectional"))
      (node (ref "DD9") (pin "37") (pinfunction "D0_37") (pintype "bidirectional"))
      (node (ref "R25") (pin "1") (pinfunction "1_1") (pintype "passive"))
    )
    (net (code "38") (name "/D1") (class "Default")
      (node (ref "DD1") (pin "15") (pinfunction "D1_15") (pintype "bidirectional"))
      (node (ref "DD10") (pin "8") (pinfunction "A7_8") (pintype "bidirectional"))
      (node (ref "DD3") (pin "15") (pinfunction "I/O3_15") (pintype "bidirectional"))
      (node (ref "DD7") (pin "39") (pinfunction "(ADC1)PA1_39") (pintype "bidirectional"))
      (node (ref "DD8") (pin "14") (pinfunction "D1_14") (pintype "bidirectional"))
      (node (ref "DD9") (pin "36") (pinfunction "D1_36") (pintype "bidirectional"))
      (node (ref "R26") (pin "1") (pinfunction "1_1") (pintype "passive"))
    )
    (net (code "39") (name "/D2") (class "Default")
      (node (ref "DD1") (pin "12") (pinfunction "D2_12") (pintype "bidirectional"))
      (node (ref "DD7") (pin "38") (pinfunction "(ADC2)PA2_38") (pintype "bidirectional"))
      (node (ref "DD9") (pin "35") (pinfunction "D2_35") (pintype "bidirectional"))
      (node (ref "J1") (pin "1") (pinfunction "1_1") (pintype "passive"))
      (node (ref "R27") (pin "1") (pinfunction "1_1") (pintype "passive"))
    )
    (net (code "40") (name "/D2.") (class "Default")
      (node (ref "DD10") (pin "9") (pinfunction "A8_9") (pintype "bidirectional"))
      (node (ref "DD3") (pin "17") (pinfunction "I/O4_17") (pintype "bidirectional"))
      (node (ref "DD8") (pin "15") (pinfunction "D2_15") (pintype "bidirectional"))
      (node (ref "J1") (pin "2") (pinfunction "2_2") (pintype "passive"))
    )
    (net (code "41") (name "/D3") (class "Default")
      (node (ref "DD1") (pin "8") (pinfunction "D3_8") (pintype "bidirectional"))
      (node (ref "DD10") (pin "2") (pinfunction "A1_2") (pintype "bidirectional"))
      (node (ref "DD3") (pin "21") (pinfunction "I/O8_21") (pintype "bidirectional"))
      (node (ref "DD7") (pin "37") (pinfunction "(ADC3)PA3_37") (pintype "bidirectional"))
      (node (ref "DD8") (pin "17") (pinfunction "D3_17") (pintype "bidirectional"))
      (node (ref "DD9") (pin "34") (pinfunction "D3_34") (pintype "bidirectional"))
      (node (ref "R28") (pin "1") (pinfunction "1_1") (pintype "passive"))
    )
    (net (code "42") (name "/D4") (class "Default")
      (node (ref "DD1") (pin "7") (pinfunction "D4_7") (pintype "bidirectional"))
      (node (ref "DD10") (pin "3") (pinfunction "A2_3") (pintype "bidirectional"))
      (node (ref "DD3") (pin "20") (pinfunction "I/O7_20") (pintype "bidirectional"))
      (node (ref "DD7") (pin "36") (pinfunction "(ADC4)PA4_36") (pintype "bidirectional"))
      (node (ref "DD8") (pin "18") (pinfunction "D4_18") (pintype "bidirectional"))
      (node (ref "DD9") (pin "33") (pinfunction "D4_33") (pintype "bidirectional"))
      (node (ref "R29") (pin "1") (pinfunction "1_1") (pintype "passive"))
    )
    (net (code "43") (name "/D5") (class "Default")
      (node (ref "DD1") (pin "9") (pinfunction "D5_9") (pintype "bidirectional"))
      (node (ref "DD10") (pin "4") (pinfunction "A3_4") (pintype "bidirectional"))
      (node (ref "DD3") (pin "13") (pinfunction "I/O1_13") (pintype "bidirectional"))
      (node (ref "DD7") (pin "35") (pinfunction "(ADC5)PA5_35") (pintype "bidirectional"))
      (node (ref "DD8") (pin "19") (pinfunction "D5_19") (pintype "bidirectional"))
      (node (ref "DD9") (pin "32") (pinfunction "D5_32") (pintype "bidirectional"))
      (node (ref "R30") (pin "1") (pinfunction "1_1") (pintype "passive"))
    )
    (net (code "44") (name "/D6") (class "Default")
      (node (ref "DD1") (pin "10") (pinfunction "D6_10") (pintype "bidirectional"))
      (node (ref "DD10") (pin "5") (pinfunction "A4_5") (pintype "bidirectional"))
      (node (ref "DD3") (pin "19") (pinfunction "I/O6_19") (pintype "bidirectional"))
      (node (ref "DD7") (pin "34") (pinfunction "(ADC6)PA6_34") (pintype "bidirectional"))
      (node (ref "DD8") (pin "20") (pinfunction "D6_20") (pintype "bidirectional"))
      (node (ref "DD9") (pin "31") (pinfunction "D6_31") (pintype "bidirectional"))
      (node (ref "R31") (pin "1") (pinfunction "1_1") (pintype "passive"))
    )
    (net (code "45") (name "/D7") (class "Default")
      (node (ref "DD1") (pin "13") (pinfunction "D7_13") (pintype "bidirectional"))
      (node (ref "DD10") (pin "6") (pinfunction "A5_6") (pintype "bidirectional"))
      (node (ref "DD3") (pin "14") (pinfunction "I/O2_14") (pintype "bidirectional"))
      (node (ref "DD7") (pin "33") (pinfunction "(ADC7)PA7_33") (pintype "bidirectional"))
      (node (ref "DD8") (pin "21") (pinfunction "D7_21") (pintype "bidirectional"))
      (node (ref "DD9") (pin "30") (pinfunction "D7_30") (pintype "bidirectional"))
      (node (ref "R32") (pin "1") (pinfunction "1_1") (pintype "passive"))
    )
    (net (code "46") (name "/FC") (class "Default")
      (node (ref "C12P") (pin "1") (pinfunction "1_1") (pintype "passive"))
      (node (ref "DD12") (pin "9") (pinfunction "Q_9") (pintype "output"))
      (node (ref "J3") (pin "2") (pinfunction "2_2") (pintype "passive"))
    )
    (net (code "47") (name "/FCI") (class "Default")
      (node (ref "DD11") (pin "8") (pinfunction "O_8") (pintype "output"))
      (node (ref "DD12") (pin "11") (pinfunction "CLK_11") (pintype "input"))
      (node (ref "J3") (pin "1") (pinfunction "1_1") (pintype "passive"))
    )
    (net (code "48") (name "/G") (class "Default")
      (node (ref "DD2") (pin "34") (pinfunction "IO61_34") (pintype "bidirectional"))
      (node (ref "R9") (pin "1") (pinfunction "1_1") (pintype "passive"))
    )
    (net (code "49") (name "/G_OUT") (class "Default")
      (node (ref "DA1") (pin "22") (pinfunction "22_22") (pintype "passive"))
      (node (ref "R10P") (pin "1") (pinfunction "1_1") (pintype "passive"))
    )
    (net (code "50") (name "/INT") (class "Default")
      (node (ref "DD1") (pin "16") (pinfunction "INT_16") (pintype "input"))
      (node (ref "DD2") (pin "21") (pinfunction "IO19_21") (pintype "bidirectional"))
    )
    (net (code "51") (name "/IOREQ") (class "Default")
      (node (ref "DD1") (pin "20") (pinfunction "IORQ_20") (pintype "output"))
      (node (ref "DD2") (pin "20") (pinfunction "IO21_20") (pintype "bidirectional"))
    )
    (net (code "52") (name "/KCLK") (class "Default")
      (node (ref "DD7") (pin "16") (pinfunction "(INT0)PD2_16") (pintype "bidirectional"))
      (node (ref "R23") (pin "2") (pinfunction "2_2") (pintype "passive"))
      (node (ref "X3") (pin "5") (pinfunction "5_5") (pintype "passive"))
      (node (ref "X3P") (pin "1") (pinfunction "1_1") (pintype "passive"))
    )
    (net (code "53") (name "/KDAT") (class "Default")
      (node (ref "DD7") (pin "3") (pinfunction "(AIN0/INT2)PB2_3") (pintype "bidirectional"))
      (node (ref "J2") (pin "1") (pinfunction "1_1") (pintype "passive"))
    )
    (net (code "54") (name "/KDATR") (class "Default")
      (node (ref "J2") (pin "2") (pinfunction "2_2") (pintype "passive"))
      (node (ref "R22") (pin "1") (pinfunction "1_1") (pintype "passive"))
      (node (ref "X3") (pin "1") (pinfunction "1_1") (pintype "passive"))
      (node (ref "X3P") (pin "2") (pinfunction "2_2") (pintype "passive"))
    )
    (net (code "55") (name "/M1") (class "Default")
      (node (ref "DD1") (pin "27") (pinfunction "M1_27") (pintype "output"))
      (node (ref "DD2") (pin "16") (pinfunction "IO27_16") (pintype "bidirectional"))
    )
    (net (code "56") (name "/MISO") (class "Default")
      (node (ref "DD7") (pin "7") (pinfunction "(MISO)PB6_7") (pintype "bidirectional"))
      (node (ref "R11") (pin "1") (pinfunction "1_1") (pintype "passive"))
      (node (ref "X4") (pin "7") (pinfunction "DAT0/DO_7") (pintype "bidirectional"))
      (node (ref "X6") (pin "1") (pinfunction "1_1") (pintype "passive"))
    )
    (net (code "57") (name "/MOSI") (class "Default")
      (node (ref "DD7") (pin "6") (pinfunction "(MOSI)PB5_6") (pintype "bidirectional"))
      (node (ref "R15") (pin "2") (pinfunction "2_2") (pintype "passive"))
      (node (ref "X6") (pin "4") (pinfunction "4_4") (pintype "passive"))
    )
    (net (code "58") (name "/MREQ") (class "Default")
      (node (ref "DD1") (pin "19") (pinfunction "MREQ_19") (pintype "output"))
      (node (ref "DD2") (pin "18") (pinfunction "IO24_18") (pintype "bidirectional"))
    )
    (net (code "59") (name "/NMI") (class "Default")
      (node (ref "DD1") (pin "17") (pinfunction "NMI_17") (pintype "input"))
      (node (ref "DD7") (pin "2") (pinfunction "(T1)PB1_2") (pintype "bidirectional"))
    )
    (net (code "60") (name "/R") (class "Default")
      (node (ref "DD2") (pin "30") (pinfunction "IO37_30") (pintype "bidirectional"))
      (node (ref "R8") (pin "1") (pinfunction "1_1") (pintype "passive"))
    )
    (net (code "61") (name "/RA14") (class "Default")
      (node (ref "DD2") (pin "75") (pinfunction "IO118_75") (pintype "bidirectional"))
      (node (ref "DD3") (pin "10") (pinfunction "A2_10") (pintype "input"))
    )
    (net (code "62") (name "/RA15") (class "Default")
      (node (ref "DD2") (pin "74") (pinfunction "IO117_74") (pintype "bidirectional"))
      (node (ref "DD3") (pin "12") (pinfunction "A0_12") (pintype "input"))
    )
    (net (code "63") (name "/RA16") (class "Default")
      (node (ref "DD2") (pin "73") (pinfunction "IO115_73") (pintype "bidirectional"))
      (node (ref "DD3") (pin "11") (pinfunction "A1_11") (pintype "input"))
    )
    (net (code "64") (name "/RAM_CS") (class "Default")
      (node (ref "DD2") (pin "11") (pinfunction "IO5_11") (pintype "bidirectional"))
      (node (ref "DD3") (pin "22") (pinfunction "~{CS1}_22") (pintype "input"))
    )
    (net (code "65") (name "/RD") (class "Default")
      (node (ref "DD1") (pin "21") (pinfunction "RD_21") (pintype "output"))
      (node (ref "DD2") (pin "4") (pinfunction "IO16_4") (pintype "bidirectional"))
      (node (ref "DD3") (pin "24") (pinfunction "~{OE}_24") (pintype "input"))
      (node (ref "DD8") (pin "24") (pinfunction "~{OE}_24") (pintype "input"))
    )
    (net (code "66") (name "/ROM_A14") (class "Default")
      (node (ref "DD2") (pin "31") (pinfunction "IO35_31") (pintype "bidirectional"))
      (node (ref "DD8") (pin "29") (pinfunction "A14_29") (pintype "input"))
    )
    (net (code "67") (name "/ROM_A15") (class "Default")
      (node (ref "DD2") (pin "37") (pinfunction "IO56_37") (pintype "bidirectional"))
      (node (ref "DD8") (pin "3") (pinfunction "A15_3") (pintype "input"))
    )
    (net (code "68") (name "/ROM_CS") (class "Default")
      (node (ref "DD2") (pin "5") (pinfunction "IO14_5") (pintype "bidirectional"))
      (node (ref "DD8") (pin "22") (pinfunction "~{CE}_22") (pintype "input"))
    )
    (net (code "69") (name "/RST_CPU") (class "Default")
      (node (ref "DD1") (pin "26") (pinfunction "RESET_26") (pintype "input"))
      (node (ref "DD2") (pin "1") (pinfunction "GCLR/_1") (pintype "input"))
      (node (ref "DD7") (pin "1") (pinfunction "(T0/XCK)PB0_1") (pintype "bidirectional"))
      (node (ref "DD9") (pin "23") (pinfunction "~{RES}_23") (pintype "bidirectional"))
      (node (ref "R20") (pin "2") (pinfunction "2_2") (pintype "passive"))
    )
    (net (code "70") (name "/R_OUT") (class "Default")
      (node (ref "DA1") (pin "23") (pinfunction "23_23") (pintype "passive"))
      (node (ref "JP2") (pin "1") (pinfunction "1_1") (pintype "passive"))
    )
    (net (code "71") (name "/SCK") (class "Default")
      (node (ref "DD7") (pin "8") (pinfunction "(SCK)PB7_8") (pintype "bidirectional"))
      (node (ref "R13") (pin "2") (pinfunction "2_2") (pintype "passive"))
      (node (ref "X6") (pin "3") (pinfunction "3_3") (pintype "passive"))
    )
    (net (code "72") (name "/SDC") (class "Default")
      (node (ref "DD7") (pin "5") (pinfunction "(SS)PB4_5") (pintype "bidirectional"))
      (node (ref "R17") (pin "2") (pinfunction "2_2") (pintype "passive"))
    )
    (net (code "73") (name "/SOUND_L") (class "Default")
      (node (ref "C2Y") (pin "-") (pinfunction "-_-") (pintype "passive"))
      (node (ref "X2") (pin "3") (pinfunction "3_3") (pintype "passive"))
    )
    (net (code "74") (name "/SOUND_R") (class "Default")
      (node (ref "C1Y") (pin "-") (pinfunction "-_-") (pintype "passive"))
      (node (ref "X2") (pin "1") (pinfunction "1_1") (pintype "passive"))
    )
    (net (code "75") (name "/SPEAKER") (class "Default")
      (node (ref "DD2") (pin "35") (pinfunction "IO59_35") (pintype "bidirectional"))
      (node (ref "R49") (pin "2") (pinfunction "2_2") (pintype "passive"))
    )
    (net (code "76") (name "/SYNC") (class "Default")
      (node (ref "DD2") (pin "36") (pinfunction "IO57_36") (pintype "bidirectional"))
      (node (ref "R4") (pin "1") (pinfunction "1_1") (pintype "passive"))
    )
    (net (code "77") (name "/S_A") (class "Default")
      (node (ref "DD9") (pin "4") (pinfunction "A_4") (pintype "bidirectional"))
      (node (ref "R41") (pin "1") (pinfunction "1_1") (pintype "passive"))
    )
    (net (code "78") (name "/S_B") (class "Default")
      (node (ref "DD9") (pin "3") (pinfunction "B_3") (pintype "bidirectional"))
      (node (ref "R42") (pin "1") (pinfunction "1_1") (pintype "passive"))
      (node (ref "R43") (pin "1") (pinfunction "1_1") (pintype "passive"))
    )
    (net (code "79") (name "/S_C") (class "Default")
      (node (ref "DD9") (pin "38") (pinfunction "C_38") (pintype "bidirectional"))
      (node (ref "R44") (pin "1") (pinfunction "1_1") (pintype "passive"))
    )
    (net (code "80") (name "/TAPE_IN") (class "Default")
      (node (ref "DD2") (pin "12") (pinfunction "IO3_12") (pintype "bidirectional"))
      (node (ref "DD7") (pin "21") (pinfunction "(OC2)PD7_21") (pintype "bidirectional"))
    )
    (net (code "81") (name "/TCK") (class "Default")
      (node (ref "DD2") (pin "62") (pinfunction "TCK/IO96_62") (pintype "bidirectional"))
      (node (ref "X5") (pin "1") (pinfunction "1_1") (pintype "passive"))
    )
    (net (code "82") (name "/TDI") (class "Default")
      (node (ref "DD2") (pin "14") (pinfunction "IO32/TDI_14") (pintype "bidirectional"))
      (node (ref "X5") (pin "9") (pinfunction "9_9") (pintype "passive"))
    )
    (net (code "83") (name "/TDO") (class "Default")
      (node (ref "DD2") (pin "71") (pinfunction "TDO/IO112_71") (pintype "bidirectional"))
      (node (ref "X5") (pin "3") (pinfunction "3_3") (pintype "passive"))
    )
    (net (code "84") (name "/TMS") (class "Default")
      (node (ref "DD2") (pin "23") (pinfunction "IO48/TMS_23") (pintype "bidirectional"))
      (node (ref "X5") (pin "5") (pinfunction "5_5") (pintype "passive"))
    )
    (net (code "85") (name "/VA0") (class "Default")
      (node (ref "DD2") (pin "56") (pinfunction "IO86_56") (pintype "bidirectional"))
      (node (ref "DD5") (pin "11") (pinfunction "B8_11") (pintype "bidirectional"))
      (node (ref "DD6") (pin "21") (pinfunction "A10_21") (pintype "input"))
    )
    (net (code "86") (name "/VA1") (class "Default")
      (node (ref "DD2") (pin "52") (pinfunction "IO80_52") (pintype "bidirectional"))
      (node (ref "DD5") (pin "12") (pinfunction "B7_12") (pintype "bidirectional"))
      (node (ref "DD6") (pin "6") (pinfunction "A4_6") (pintype "input"))
      (node (ref "DD6") (pin "P$6") (pinfunction "A4_P$6") (pintype "input"))
    )
    (net (code "87") (name "/VA2") (class "Default")
      (node (ref "DD2") (pin "50") (pinfunction "IO75_50") (pintype "bidirectional"))
      (node (ref "DD5") (pin "13") (pinfunction "B6_13") (pintype "bidirectional"))
      (node (ref "DD6") (pin "5") (pinfunction "A5_5") (pintype "input"))
      (node (ref "DD6") (pin "P$5") (pinfunction "A5_P$5") (pintype "input"))
    )
    (net (code "88") (name "/VA3") (class "Default")
      (node (ref "DD2") (pin "48") (pinfunction "IO72_48") (pintype "bidirectional"))
      (node (ref "DD5") (pin "14") (pinfunction "B5_14") (pintype "bidirectional"))
      (node (ref "DD6") (pin "4") (pinfunction "A6_4") (pintype "input"))
      (node (ref "DD6") (pin "P$4") (pinfunction "A6_P$4") (pintype "input"))
    )
    (net (code "89") (name "/VA4") (class "Default")
      (node (ref "DD2") (pin "45") (pinfunction "IO67_45") (pintype "bidirectional"))
      (node (ref "DD5") (pin "15") (pinfunction "B4_15") (pintype "bidirectional"))
      (node (ref "DD6") (pin "3") (pinfunction "A7_3") (pintype "input"))
      (node (ref "DD6") (pin "P$3") (pinfunction "A7_P$3") (pintype "input"))
    )
    (net (code "90") (name "/VA5") (class "Default")
      (node (ref "DD2") (pin "40") (pinfunction "IO51_40") (pintype "bidirectional"))
      (node (ref "DD5") (pin "16") (pinfunction "B3_16") (pintype "bidirectional"))
      (node (ref "DD6") (pin "1") (pinfunction "A14_1") (pintype "input"))
      (node (ref "DD6") (pin "P$1") (pinfunction "A14_P$1") (pintype "input"))
    )
    (net (code "91") (name "/VA6") (class "Default")
      (node (ref "DD2") (pin "39") (pinfunction "IO53_39") (pintype "bidirectional"))
      (node (ref "DD4") (pin "18") (pinfunction "B1_18") (pintype "bidirectional"))
      (node (ref "DD6") (pin "2") (pinfunction "A12_2") (pintype "input"))
      (node (ref "DD6") (pin "P$2") (pinfunction "A12_P$2") (pintype "input"))
    )
    (net (code "92") (name "/VA7") (class "Default")
      (node (ref "DD2") (pin "44") (pinfunction "IO65_44") (pintype "bidirectional"))
      (node (ref "DD4") (pin "17") (pinfunction "B2_17") (pintype "bidirectional"))
      (node (ref "DD6") (pin "26") (pinfunction "A13_26") (pintype "input"))
    )
    (net (code "93") (name "/VA8") (class "Default")
      (node (ref "DD2") (pin "46") (pinfunction "IO69_46") (pintype "bidirectional"))
      (node (ref "DD4") (pin "16") (pinfunction "B3_16") (pintype "bidirectional"))
      (node (ref "DD6") (pin "25") (pinfunction "A8_25") (pintype "input"))
    )
    (net (code "94") (name "/VA9") (class "Default")
      (node (ref "DD2") (pin "49") (pinfunction "IO73_49") (pintype "bidirectional"))
      (node (ref "DD4") (pin "15") (pinfunction "B4_15") (pintype "bidirectional"))
      (node (ref "DD6") (pin "24") (pinfunction "A9_24") (pintype "input"))
    )
    (net (code "95") (name "/VA10") (class "Default")
      (node (ref "DD2") (pin "51") (pinfunction "IO77_51") (pintype "bidirectional"))
      (node (ref "DD4") (pin "14") (pinfunction "B5_14") (pintype "bidirectional"))
      (node (ref "DD6") (pin "23") (pinfunction "A11_23") (pintype "input"))
    )
    (net (code "96") (name "/VA11") (class "Default")
      (node (ref "DD2") (pin "55") (pinfunction "IO85_55") (pintype "bidirectional"))
      (node (ref "DD4") (pin "13") (pinfunction "B6_13") (pintype "bidirectional"))
      (node (ref "DD6") (pin "7") (pinfunction "A3_7") (pintype "input"))
      (node (ref "DD6") (pin "P$7") (pinfunction "A3_P$7") (pintype "input"))
    )
    (net (code "97") (name "/VA12") (class "Default")
      (node (ref "DD2") (pin "57") (pinfunction "IO88_57") (pintype "bidirectional"))
      (node (ref "DD4") (pin "12") (pinfunction "B7_12") (pintype "bidirectional"))
      (node (ref "DD6") (pin "8") (pinfunction "A2_8") (pintype "input"))
      (node (ref "DD6") (pin "P$8") (pinfunction "A2_P$8") (pintype "input"))
    )
    (net (code "98") (name "/VA13") (class "Default")
      (node (ref "DD2") (pin "60") (pinfunction "IO93_60") (pintype "bidirectional"))
      (node (ref "DD4") (pin "11") (pinfunction "B8_11") (pintype "bidirectional"))
      (node (ref "DD6") (pin "9") (pinfunction "A1_9") (pintype "input"))
      (node (ref "DD6") (pin "P$9") (pinfunction "A1_P$9") (pintype "input"))
    )
    (net (code "99") (name "/VA14") (class "Default")
      (node (ref "DD2") (pin "76") (pinfunction "IO120_76") (pintype "bidirectional"))
      (node (ref "DD6") (pin "10") (pinfunction "A0_10") (pintype "input"))
      (node (ref "DD6") (pin "P$10") (pinfunction "A0_P$10") (pintype "input"))
    )
    (net (code "100") (name "/VAGEN") (class "Default")
      (node (ref "DD10") (pin "19") (pinfunction "G_19") (pintype "input"))
      (node (ref "DD2") (pin "10") (pinfunction "IO6_10") (pintype "bidirectional"))
      (node (ref "DD4") (pin "19") (pinfunction "G_19") (pintype "input"))
      (node (ref "DD5") (pin "19") (pinfunction "G_19") (pintype "input"))
    )
    (net (code "101") (name "/VD0") (class "Default")
      (node (ref "DD10") (pin "13") (pinfunction "B6_13") (pintype "bidirectional"))
      (node (ref "DD2") (pin "68") (pinfunction "IO105_68") (pintype "bidirectional"))
      (node (ref "DD6") (pin "16") (pinfunction "I/O4_16") (pintype "bidirectional"))
    )
    (net (code "102") (name "/VD1") (class "Default")
      (node (ref "DD10") (pin "12") (pinfunction "B7_12") (pintype "bidirectional"))
      (node (ref "DD2") (pin "69") (pinfunction "IO107_69") (pintype "bidirectional"))
      (node (ref "DD6") (pin "13") (pinfunction "I/O2_13") (pintype "bidirectional"))
      (node (ref "DD6") (pin "P$13") (pinfunction "I/O2_P$13") (pintype "bidirectional"))
    )
    (net (code "103") (name "/VD2") (class "Default")
      (node (ref "DD10") (pin "11") (pinfunction "B8_11") (pintype "bidirectional"))
      (node (ref "DD2") (pin "70") (pinfunction "IO109_70") (pintype "bidirectional"))
      (node (ref "DD6") (pin "15") (pinfunction "I/O3_15") (pintype "bidirectional"))
    )
    (net (code "104") (name "/VD3") (class "Default")
      (node (ref "DD10") (pin "18") (pinfunction "B1_18") (pintype "bidirectional"))
      (node (ref "DD2") (pin "61") (pinfunction "IO94_61") (pintype "bidirectional"))
      (node (ref "DD6") (pin "19") (pinfunction "I/O7_19") (pintype "bidirectional"))
    )
    (net (code "105") (name "/VD4") (class "Default")
      (node (ref "DD10") (pin "17") (pinfunction "B2_17") (pintype "bidirectional"))
      (node (ref "DD2") (pin "63") (pinfunction "IO97_63") (pintype "bidirectional"))
      (node (ref "DD6") (pin "18") (pinfunction "I/O6_18") (pintype "bidirectional"))
    )
    (net (code "106") (name "/VD5") (class "Default")
      (node (ref "DD10") (pin "16") (pinfunction "B3_16") (pintype "bidirectional"))
      (node (ref "DD2") (pin "64") (pinfunction "IO99_64") (pintype "bidirectional"))
      (node (ref "DD6") (pin "11") (pinfunction "I/O0_11") (pintype "bidirectional"))
      (node (ref "DD6") (pin "P$11") (pinfunction "I/O0_P$11") (pintype "bidirectional"))
    )
    (net (code "107") (name "/VD6") (class "Default")
      (node (ref "DD10") (pin "15") (pinfunction "B4_15") (pintype "bidirectional"))
      (node (ref "DD2") (pin "65") (pinfunction "IO101_65") (pintype "bidirectional"))
      (node (ref "DD6") (pin "17") (pinfunction "I/O5_17") (pintype "bidirectional"))
    )
    (net (code "108") (name "/VD7") (class "Default")
      (node (ref "DD10") (pin "14") (pinfunction "B5_14") (pintype "bidirectional"))
      (node (ref "DD2") (pin "67") (pinfunction "IO104_67") (pintype "bidirectional"))
      (node (ref "DD6") (pin "12") (pinfunction "I/O1_12") (pintype "bidirectional"))
      (node (ref "DD6") (pin "P$12") (pinfunction "I/O1_P$12") (pintype "bidirectional"))
    )
    (net (code "109") (name "/VRAM") (class "Default")
      (node (ref "DD2") (pin "58") (pinfunction "IO91_58") (pintype "bidirectional"))
      (node (ref "DD6") (pin "20") (pinfunction "~{CS}_20") (pintype "input"))
    )
    (net (code "110") (name "/VRD") (class "Default")
      (node (ref "DD2") (pin "54") (pinfunction "IO83_54") (pintype "bidirectional"))
      (node (ref "DD6") (pin "22") (pinfunction "~{OE}_22") (pintype "input"))
    )
    (net (code "111") (name "/VWR") (class "Default")
      (node (ref "DD2") (pin "41") (pinfunction "IO49_41") (pintype "bidirectional"))
      (node (ref "DD6") (pin "27") (pinfunction "~{WE}_27") (pintype "input"))
    )
    (net (code "112") (name "/V_OUT") (class "Default")
      (node (ref "DA1") (pin "20") (pinfunction "20_20") (pintype "passive"))
      (node (ref "JP1") (pin "1") (pinfunction "1_1") (pintype "passive"))
    )
    (net (code "113") (name "/WAIT_CPU") (class "Default")
      (node (ref "DD1") (pin "24") (pinfunction "WAIT_24") (pintype "input"))
      (node (ref "DD2") (pin "17") (pinfunction "IO25_17") (pintype "bidirectional"))
      (node (ref "R142") (pin "2") (pinfunction "2_2") (pintype "passive"))
    )
    (net (code "114") (name "/WR") (class "Default")
      (node (ref "DD1") (pin "22") (pinfunction "WR_22") (pintype "output"))
      (node (ref "DD2") (pin "8") (pinfunction "IO11_8") (pintype "bidirectional"))
      (node (ref "DD3") (pin "29") (pinfunction "~{WE}_29") (pintype "input"))
      (node (ref "DD7") (pin "18") (pinfunction "(OC1B)PD4_18") (pintype "bidirectional"))
    )
    (net (code "115") (name "/Y_OUT") (class "Default")
      (node (ref "DA1") (pin "16") (pinfunction "16_16") (pintype "passive"))
      (node (ref "JP1") (pin "3") (pinfunction "3_3") (pintype "passive"))
    )
    (net (code "116") (name "GND") (class "Default")
      (node (ref "C1") (pin "-") (pinfunction "-_-") (pintype "passive"))
      (node (ref "C10") (pin "2") (pinfunction "2_2") (pintype "passive"))
      (node (ref "C12") (pin "2") (pinfunction "2_2") (pintype "passive"))
      (node (ref "C13") (pin "2") (pinfunction "2_2") (pintype "passive"))
      (node (ref "C14") (pin "2") (pinfunction "2_2") (pintype "passive"))
      (node (ref "C15") (pin "2") (pinfunction "2_2") (pintype "passive"))
      (node (ref "C16") (pin "2") (pinfunction "2_2") (pintype "passive"))
      (node (ref "C17") (pin "-") (pinfunction "-_-") (pintype "passive"))
      (node (ref "C2") (pin "2") (pinfunction "2_2") (pintype "passive"))
      (node (ref "C3") (pin "2") (pinfunction "2_2") (pintype "passive"))
      (node (ref "C4") (pin "2") (pinfunction "2_2") (pintype "passive"))
      (node (ref "C4P") (pin "1") (pinfunction "1_1") (pintype "passive"))
      (node (ref "C5") (pin "2") (pinfunction "2_2") (pintype "passive"))
      (node (ref "C5P") (pin "1") (pinfunction "1_1") (pintype "passive"))
      (node (ref "C6") (pin "2") (pinfunction "2_2") (pintype "passive"))
      (node (ref "C6P") (pin "-") (pinfunction "-_-") (pintype "passive"))
      (node (ref "C7") (pin "2") (pinfunction "2_2") (pintype "passive"))
      (node (ref "C7P*") (pin "2") (pinfunction "2_2") (pintype "passive"))
      (node (ref "C8") (pin "2") (pinfunction "2_2") (pintype "passive"))
      (node (ref "C9") (pin "-") (pinfunction "-_-") (pintype "passive"))
      (node (ref "DA1") (pin "1") (pinfunction "1_1") (pintype "passive"))
      (node (ref "DA1") (pin "24") (pinfunction "24_24") (pintype "passive"))
      (node (ref "DA1") (pin "7") (pinfunction "7_7") (pintype "passive"))
      (node (ref "DA2") (pin "1") (pinfunction "GND_1") (pintype "power_in"))
      (node (ref "DD1") (pin "29") (pinfunction "GND_29") (pintype "power_in"))
      (node (ref "DD10") (pin "10") (pinfunction "GND_10") (pintype "power_in"))
      (node (ref "DD11") (pin "7") (pinfunction "GND_7") (pintype "power_in"))
      (node (ref "DD12") (pin "7") (pinfunction "GND_7") (pintype "power_in"))
      (node (ref "DD2") (pin "19") (pinfunction "GND_19") (pintype "power_in"))
      (node (ref "DD2") (pin "32") (pinfunction "GND_32") (pintype "power_in"))
      (node (ref "DD2") (pin "42") (pinfunction "GND_42") (pintype "power_in"))
      (node (ref "DD2") (pin "47") (pinfunction "GND_47") (pintype "power_in"))
      (node (ref "DD2") (pin "59") (pinfunction "GND_59") (pintype "power_in"))
      (node (ref "DD2") (pin "7") (pinfunction "GND_7") (pintype "power_in"))
      (node (ref "DD2") (pin "72") (pinfunction "GND_72") (pintype "power_in"))
      (node (ref "DD2") (pin "82") (pinfunction "GND_82") (pintype "power_in"))
      (node (ref "DD3") (pin "16") (pinfunction "GND_16") (pintype "power_in"))
      (node (ref "DD4") (pin "10") (pinfunction "GND_10") (pintype "power_in"))
      (node (ref "DD5") (pin "10") (pinfunction "GND_10") (pintype "power_in"))
      (node (ref "DD6") (pin "14") (pinfunction "VSS_14") (pintype "power_in"))
      (node (ref "DD6") (pin "P$14") (pinfunction "VSS_P$14") (pintype "power_in"))
      (node (ref "DD7") (pin "11") (pinfunction "GND_11") (pintype "power_in"))
      (node (ref "DD7") (pin "31") (pinfunction "GND_31") (pintype "power_in"))
      (node (ref "DD8") (pin "16") (pinfunction "GND_16") (pintype "power_in"))
      (node (ref "DD8") (pin "2") (pinfunction "A16_2") (pintype "input"))
      (node (ref "DD8") (pin "30") (pinfunction "A17_30") (pintype "input"))
      (node (ref "DD9") (pin "1") (pinfunction "GND_1") (pintype "bidirectional"))
      (node (ref "DD9") (pin "24") (pinfunction "CS2_24") (pintype "bidirectional"))
      (node (ref "R12") (pin "1") (pinfunction "1_1") (pintype "passive"))
      (node (ref "R14") (pin "1") (pinfunction "1_1") (pintype "passive"))
      (node (ref "R18") (pin "1") (pinfunction "1_1") (pintype "passive"))
      (node (ref "R34") (pin "1") (pinfunction "1_1") (pintype "passive"))
      (node (ref "R45") (pin "2") (pinfunction "2_2") (pintype "passive"))
      (node (ref "R48") (pin "2") (pinfunction "2_2") (pintype "passive"))
      (node (ref "R5P*") (pin "1") (pinfunction "1_1") (pintype "passive"))
      (node (ref "R6P") (pin "1") (pinfunction "1_1") (pintype "passive"))
      (node (ref "R_B") (pin "3") (pinfunction "A_3") (pintype "passive"))
      (node (ref "R_G") (pin "3") (pinfunction "A_3") (pintype "passive"))
      (node (ref "R_R") (pin "3") (pinfunction "A_3") (pintype "passive"))
      (node (ref "R_SY") (pin "3") (pinfunction "A_3") (pintype "passive"))
      (node (ref "VT1") (pin "E") (pinfunction "E_E") (pintype "passive"))
      (node (ref "X1") (pin "P$2") (pinfunction "2_P$2") (pintype "passive"))
      (node (ref "X1") (pin "P$3") (pinfunction "3_P$3") (pintype "passive"))
      (node (ref "X2") (pin "13") (pinfunction "13_13") (pintype "passive"))
      (node (ref "X2") (pin "14") (pinfunction "14_14") (pintype "passive"))
      (node (ref "X2") (pin "17") (pinfunction "17_17") (pintype "passive"))
      (node (ref "X2") (pin "18") (pinfunction "18_18") (pintype "passive"))
      (node (ref "X2") (pin "21") (pinfunction "21_21") (pintype "passive"))
      (node (ref "X2") (pin "4") (pinfunction "4_4") (pintype "passive"))
      (node (ref "X2") (pin "5") (pinfunction "5_5") (pintype "passive"))
      (node (ref "X2") (pin "9") (pinfunction "9_9") (pintype "passive"))
      (node (ref "X3") (pin "3") (pinfunction "3_3") (pintype "passive"))
      (node (ref "X3") (pin "GND") (pinfunction "7_GND") (pintype "passive"))
      (node (ref "X3P") (pin "4") (pinfunction "4_4") (pintype "passive"))
      (node (ref "X4") (pin "3") (pinfunction "VSS1_3") (pintype "power_in"))
      (node (ref "X4") (pin "6") (pinfunction "VSS2_6") (pintype "power_in"))
      (node (ref "X4") (pin "M1") (pinfunction "GND_M1") (pintype "power_in"))
      (node (ref "X4") (pin "M2") (pinfunction "GND_M2") (pintype "power_in"))
      (node (ref "X4") (pin "M3") (pinfunction "GND_M3") (pintype "power_in"))
      (node (ref "X4") (pin "M4") (pinfunction "GND_M4") (pintype "power_in"))
      (node (ref "X5") (pin "10") (pinfunction "10_10") (pintype "passive"))
      (node (ref "X5") (pin "2") (pinfunction "2_2") (pintype "passive"))
      (node (ref "X6") (pin "6") (pinfunction "6_6") (pintype "passive"))
    )
    (net (code "117") (name "Net-(C1P-Pad2)") (class "Default")
      (node (ref "C1P") (pin "2") (pinfunction "2_2") (pintype "passive"))
      (node (ref "DA1") (pin "4") (pinfunction "4_4") (pintype "passive"))
    )
    (net (code "118") (name "Net-(C1Y-Pad+)") (class "Default")
      (node (ref "C1Y") (pin "+") (pinfunction "+_+") (pintype "passive"))
      (node (ref "R41") (pin "2") (pinfunction "2_2") (pintype "passive"))
      (node (ref "R42") (pin "2") (pinfunction "2_2") (pintype "passive"))
      (node (ref "R45") (pin "1") (pinfunction "1_1") (pintype "passive"))
      (node (ref "R46") (pin "1") (pinfunction "1_1") (pintype "passive"))
    )
    (net (code "119") (name "Net-(C2P-Pad2)") (class "Default")
      (node (ref "C2P") (pin "2") (pinfunction "2_2") (pintype "passive"))
      (node (ref "DA1") (pin "3") (pinfunction "3_3") (pintype "passive"))
    )
    (net (code "120") (name "Net-(C2Y-Pad+)") (class "Default")
      (node (ref "C2Y") (pin "+") (pinfunction "+_+") (pintype "passive"))
      (node (ref "R43") (pin "2") (pinfunction "2_2") (pintype "passive"))
      (node (ref "R44") (pin "2") (pinfunction "2_2") (pintype "passive"))
      (node (ref "R47") (pin "1") (pinfunction "1_1") (pintype "passive"))
      (node (ref "R48") (pin "1") (pinfunction "1_1") (pintype "passive"))
    )
    (net (code "121") (name "Net-(C3P-Pad2)") (class "Default")
      (node (ref "C3P") (pin "2") (pinfunction "2_2") (pintype "passive"))
      (node (ref "DA1") (pin "2") (pinfunction "2_2") (pintype "passive"))
    )
    (net (code "122") (name "Net-(C3Y-Pad1)") (class "Default")
      (node (ref "C3Y") (pin "1") (pinfunction "1_1") (pintype "passive"))
      (node (ref "R46") (pin "2") (pinfunction "2_2") (pintype "passive"))
      (node (ref "R47") (pin "2") (pinfunction "2_2") (pintype "passive"))
    )
    (net (code "123") (name "Net-(C3Y-Pad2)") (class "Default")
      (node (ref "C3Y") (pin "2") (pinfunction "2_2") (pintype "passive"))
      (node (ref "R49") (pin "1") (pinfunction "1_1") (pintype "passive"))
    )
    (net (code "124") (name "Net-(C4P-Pad2)") (class "Default")
      (node (ref "C4P") (pin "2") (pinfunction "2_2") (pintype "passive"))
      (node (ref "DA1") (pin "9") (pinfunction "9_9") (pintype "passive"))
    )
    (net (code "125") (name "Net-(C5P-Pad2)") (class "Default")
      (node (ref "C5P") (pin "2") (pinfunction "2_2") (pintype "passive"))
      (node (ref "DA1") (pin "13") (pinfunction "13_13") (pintype "passive"))
      (node (ref "R6P") (pin "2") (pinfunction "2_2") (pintype "passive"))
    )
    (net (code "126") (name "Net-(C6P-Pad+)") (class "Default")
      (node (ref "C6P") (pin "+") (pinfunction "+_+") (pintype "passive"))
      (node (ref "DA1") (pin "14") (pinfunction "14_14") (pintype "passive"))
    )
    (net (code "127") (name "Net-(C7P*-Pad1)") (class "Default")
      (node (ref "C7P*") (pin "1") (pinfunction "1_1") (pintype "passive"))
      (node (ref "DA1") (pin "17") (pinfunction "17_17") (pintype "passive"))
    )
    (net (code "128") (name "Net-(C8P-Pad+)") (class "Default")
      (node (ref "C8P") (pin "+") (pinfunction "+_+") (pintype "passive"))
      (node (ref "R8P") (pin "2") (pinfunction "2_2") (pintype "passive"))
    )
    (net (code "129") (name "Net-(C8P-Pad-)") (class "Default")
      (node (ref "C8P") (pin "-") (pinfunction "-_-") (pintype "passive"))
      (node (ref "X2") (pin "15") (pinfunction "15_15") (pintype "passive"))
    )
    (net (code "130") (name "Net-(C9P-Pad+)") (class "Default")
      (node (ref "C9P") (pin "+") (pinfunction "+_+") (pintype "passive"))
      (node (ref "R9P") (pin "2") (pinfunction "2_2") (pintype "passive"))
    )
    (net (code "131") (name "Net-(C9P-Pad-)") (class "Default")
      (node (ref "C9P") (pin "-") (pinfunction "-_-") (pintype "passive"))
      (node (ref "X2") (pin "19") (pinfunction "19_19") (pintype "passive"))
    )
    (net (code "132") (name "Net-(C10P-Pad+)") (class "Default")
      (node (ref "C10P") (pin "+") (pinfunction "+_+") (pintype "passive"))
      (node (ref "R10P") (pin "2") (pinfunction "2_2") (pintype "passive"))
    )
    (net (code "133") (name "Net-(C10P-Pad-)") (class "Default")
      (node (ref "C10P") (pin "-") (pinfunction "-_-") (pintype "passive"))
      (node (ref "X2") (pin "11") (pinfunction "11_11") (pintype "passive"))
    )
    (net (code "134") (name "Net-(C11P-Pad+)") (class "Default")
      (node (ref "C11P") (pin "+") (pinfunction "+_+") (pintype "passive"))
      (node (ref "R11P") (pin "2") (pinfunction "2_2") (pintype "passive"))
    )
    (net (code "135") (name "Net-(C11P-Pad-)") (class "Default")
      (node (ref "C11P") (pin "-") (pinfunction "-_-") (pintype "passive"))
      (node (ref "X2") (pin "7") (pinfunction "7_7") (pintype "passive"))
    )
    (net (code "136") (name "Net-(C12P-Pad2)") (class "Default")
      (node (ref "C12P") (pin "2") (pinfunction "2_2") (pintype "passive"))
      (node (ref "DA1") (pin "6") (pinfunction "6_6") (pintype "passive"))
    )
    (net (code "137") (name "Net-(DA1-Pad18)") (class "Default")
      (node (ref "DA1") (pin "18") (pinfunction "18_18") (pintype "passive"))
      (node (ref "R5P*") (pin "2") (pinfunction "2_2") (pintype "passive"))
    )
    (net (code "138") (name "Net-(DD4A-DIR)") (class "Default")
      (node (ref "DD4") (pin "1") (pinfunction "DIR_1") (pintype "input"))
      (node (ref "R35") (pin "1") (pinfunction "1_1") (pintype "passive"))
    )
    (net (code "139") (name "Net-(DD5A-A1)") (class "Default")
      (node (ref "DD5") (pin "1") (pinfunction "DIR_1") (pintype "input"))
      (node (ref "DD5") (pin "2") (pinfunction "A1_2") (pintype "bidirectional"))
      (node (ref "DD5") (pin "3") (pinfunction "A2_3") (pintype "bidirectional"))
      (node (ref "R36") (pin "1") (pinfunction "1_1") (pintype "passive"))
    )
    (net (code "140") (name "Net-(DD10A-DIR)") (class "Default")
      (node (ref "DD10") (pin "1") (pinfunction "DIR_1") (pintype "input"))
      (node (ref "R37") (pin "1") (pinfunction "1_1") (pintype "passive"))
    )
    (net (code "141") (name "Net-(DD11A-I)") (class "Default")
      (node (ref "DD11") (pin "1") (pinfunction "I_1") (pintype "input"))
      (node (ref "R1") (pin "1") (pinfunction "1_1") (pintype "passive"))
      (node (ref "Z1") (pin "1") (pinfunction "1_1") (pintype "passive"))
    )
    (net (code "142") (name "Net-(DD11A-O)") (class "Default")
      (node (ref "DD11") (pin "2") (pinfunction "O_2") (pintype "output"))
      (node (ref "DD11") (pin "3") (pinfunction "I_3") (pintype "input"))
      (node (ref "R1") (pin "2") (pinfunction "2_2") (pintype "passive"))
      (node (ref "R2") (pin "1") (pinfunction "1_1") (pintype "passive"))
    )
    (net (code "143") (name "Net-(DD11B-O)") (class "Default")
      (node (ref "DD11") (pin "4") (pinfunction "O_4") (pintype "output"))
      (node (ref "DD11") (pin "5") (pinfunction "I_5") (pintype "input"))
      (node (ref "R2") (pin "2") (pinfunction "2_2") (pintype "passive"))
      (node (ref "Z1") (pin "2") (pinfunction "2_2") (pintype "passive"))
    )
    (net (code "144") (name "Net-(DD11D-I)") (class "Default")
      (node (ref "DD11") (pin "13") (pinfunction "I_13") (pintype "input"))
      (node (ref "R38") (pin "1") (pinfunction "1_1") (pintype "passive"))
      (node (ref "Z2") (pin "1") (pinfunction "1_1") (pintype "passive"))
    )
    (net (code "145") (name "Net-(DD11D-O)") (class "Default")
      (node (ref "DD11") (pin "11") (pinfunction "I_11") (pintype "input"))
      (node (ref "DD11") (pin "12") (pinfunction "O_12") (pintype "output"))
      (node (ref "R38") (pin "2") (pinfunction "2_2") (pintype "passive"))
      (node (ref "R39") (pin "1") (pinfunction "1_1") (pintype "passive"))
    )
    (net (code "146") (name "Net-(DD11E-O)") (class "Default")
      (node (ref "DD11") (pin "10") (pinfunction "O_10") (pintype "output"))
      (node (ref "DD11") (pin "9") (pinfunction "I_9") (pintype "input"))
      (node (ref "R39") (pin "2") (pinfunction "2_2") (pintype "passive"))
      (node (ref "Z2") (pin "2") (pinfunction "2_2") (pintype "passive"))
    )
    (net (code "147") (name "Net-(DD12A-CLK)") (class "Default")
      (node (ref "DD12") (pin "1") (pinfunction "CLR_1") (pintype "input"))
      (node (ref "DD12") (pin "10") (pinfunction "PRE_10") (pintype "input"))
      (node (ref "DD12") (pin "13") (pinfunction "CLR_13") (pintype "input"))
      (node (ref "DD12") (pin "2") (pinfunction "D_2") (pintype "input"))
      (node (ref "DD12") (pin "3") (pinfunction "CLK_3") (pintype "input"))
      (node (ref "DD12") (pin "4") (pinfunction "PRE_4") (pintype "input"))
      (node (ref "R40") (pin "1") (pinfunction "1_1") (pintype "passive"))
    )
    (net (code "148") (name "Net-(DD12B-D)") (class "Default")
      (node (ref "DD12") (pin "12") (pinfunction "D_12") (pintype "input"))
      (node (ref "DD12") (pin "8") (pinfunction "~{Q}_8") (pintype "output"))
    )
    (net (code "149") (name "Net-(HL1-PadC)") (class "Default")
      (node (ref "HL1") (pin "C") (pinfunction "C_C") (pintype "passive"))
      (node (ref "R34") (pin "2") (pinfunction "2_2") (pintype "passive"))
    )
    (net (code "150") (name "Net-(HL2-PadC)") (class "Default")
      (node (ref "HL2") (pin "C") (pinfunction "C_C") (pintype "passive"))
      (node (ref "R33") (pin "2") (pinfunction "2_2") (pintype "passive"))
    )
    (net (code "151") (name "Net-(JP1-Pad2)") (class "Default")
      (node (ref "JP1") (pin "2") (pinfunction "2_2") (pintype "passive"))
      (node (ref "R9P") (pin "1") (pinfunction "1_1") (pintype "passive"))
    )
    (net (code "152") (name "Net-(JP2-Pad2)") (class "Default")
      (node (ref "JP2") (pin "2") (pinfunction "2_2") (pintype "passive"))
      (node (ref "R8P") (pin "1") (pinfunction "1_1") (pintype "passive"))
    )
    (net (code "153") (name "Net-(R17-Pad1)") (class "Default")
      (node (ref "R17") (pin "1") (pinfunction "1_1") (pintype "passive"))
      (node (ref "R18") (pin "2") (pinfunction "2_2") (pintype "passive"))
      (node (ref "VT1") (pin "B") (pinfunction "B_B") (pintype "passive"))
    )
    (net (code "154") (name "Net-(R_B-E)") (class "Default")
      (node (ref "R5") (pin "2") (pinfunction "2_2") (pintype "passive"))
      (node (ref "R8") (pin "2") (pinfunction "2_2") (pintype "passive"))
      (node (ref "R_B") (pin "1") (pinfunction "E_1") (pintype "passive"))
    )
    (net (code "155") (name "Net-(R_B-S)") (class "Default")
      (node (ref "C3P") (pin "1") (pinfunction "1_1") (pintype "passive"))
      (node (ref "R_B") (pin "2") (pinfunction "S_2") (pintype "passive"))
    )
    (net (code "156") (name "Net-(R_G-E)") (class "Default")
      (node (ref "R6") (pin "2") (pinfunction "2_2") (pintype "passive"))
      (node (ref "R9") (pin "2") (pinfunction "2_2") (pintype "passive"))
      (node (ref "R_G") (pin "1") (pinfunction "E_1") (pintype "passive"))
    )
    (net (code "157") (name "Net-(R_G-S)") (class "Default")
      (node (ref "C2P") (pin "1") (pinfunction "1_1") (pintype "passive"))
      (node (ref "R_G") (pin "2") (pinfunction "S_2") (pintype "passive"))
    )
    (net (code "158") (name "Net-(R_R-E)") (class "Default")
      (node (ref "R10") (pin "2") (pinfunction "2_2") (pintype "passive"))
      (node (ref "R7") (pin "2") (pinfunction "2_2") (pintype "passive"))
      (node (ref "R_R") (pin "1") (pinfunction "E_1") (pintype "passive"))
    )
    (net (code "159") (name "Net-(R_R-S)") (class "Default")
      (node (ref "C1P") (pin "1") (pinfunction "1_1") (pintype "passive"))
      (node (ref "R_R") (pin "2") (pinfunction "S_2") (pintype "passive"))
    )
    (net (code "160") (name "Net-(R_SY-E)") (class "Default")
      (node (ref "R4") (pin "2") (pinfunction "2_2") (pintype "passive"))
      (node (ref "R_SY") (pin "1") (pinfunction "E_1") (pintype "passive"))
    )
    (net (code "161") (name "Net-(R_SY-S)") (class "Default")
      (node (ref "DA1") (pin "10") (pinfunction "10_10") (pintype "passive"))
      (node (ref "R_SY") (pin "2") (pinfunction "S_2") (pintype "passive"))
    )
    (net (code "162") (name "Net-(X4-CD{slash}DAT3{slash}CS)") (class "Default")
      (node (ref "R16") (pin "1") (pinfunction "1_1") (pintype "passive"))
      (node (ref "R33") (pin "1") (pinfunction "1_1") (pintype "passive"))
      (node (ref "VT1") (pin "C") (pinfunction "C_C") (pintype "passive"))
      (node (ref "X4") (pin "1") (pinfunction "CD/DAT3/CS_1") (pintype "bidirectional"))
    )
    (net (code "163") (name "Net-(X4-CLK{slash}SCLK)") (class "Default")
      (node (ref "R12") (pin "2") (pinfunction "2_2") (pintype "passive"))
      (node (ref "R13") (pin "1") (pinfunction "1_1") (pintype "passive"))
      (node (ref "X4") (pin "5") (pinfunction "CLK/SCLK_5") (pintype "bidirectional"))
    )
    (net (code "164") (name "Net-(X4-CMD{slash}DI)") (class "Default")
      (node (ref "R14") (pin "2") (pinfunction "2_2") (pintype "passive"))
      (node (ref "R15") (pin "1") (pinfunction "1_1") (pintype "passive"))
      (node (ref "X4") (pin "2") (pinfunction "CMD/DI_2") (pintype "bidirectional"))
    )
    (net (code "165") (name "unconnected-(DA1-Pad5)") (class "Default")
      (node (ref "DA1") (pin "5") (pinfunction "5_5") (pintype "passive"))
    )
    (net (code "166") (name "unconnected-(DA1-Pad8)") (class "Default")
      (node (ref "DA1") (pin "8") (pinfunction "8_8") (pintype "passive"))
    )
    (net (code "167") (name "unconnected-(DA1-Pad11)") (class "Default")
      (node (ref "DA1") (pin "11") (pinfunction "11_11") (pintype "passive"))
    )
    (net (code "168") (name "unconnected-(DD1-BUSAK-Pad23)") (class "Default")
      (node (ref "DD1") (pin "23") (pinfunction "BUSAK_23") (pintype "output"))
    )
    (net (code "169") (name "unconnected-(DD1-HALT-Pad18)") (class "Default")
      (node (ref "DD1") (pin "18") (pinfunction "HALT_18") (pintype "output"))
    )
    (net (code "170") (name "unconnected-(DD1-RFSH-Pad28)") (class "Default")
      (node (ref "DD1") (pin "28") (pinfunction "RFSH_28") (pintype "output"))
    )
    (net (code "171") (name "unconnected-(DD2A-OE1-Pad84)") (class "Default")
      (node (ref "DD2") (pin "84") (pinfunction "OE1_84") (pintype "input"))
    )
    (net (code "172") (name "unconnected-(DD3A-NC-Pad1)") (class "Default")
      (node (ref "DD3") (pin "1") (pinfunction "NC_1") (pintype "no_connect"))
    )
    (net (code "173") (name "unconnected-(DD5A-B1-Pad18)") (class "Default")
      (node (ref "DD5") (pin "18") (pinfunction "B1_18") (pintype "bidirectional"))
    )
    (net (code "174") (name "unconnected-(DD5A-B2-Pad17)") (class "Default")
      (node (ref "DD5") (pin "17") (pinfunction "B2_17") (pintype "bidirectional"))
    )
    (net (code "175") (name "unconnected-(DD7-AREF-Pad32)") (class "Default")
      (node (ref "DD7") (pin "32") (pinfunction "AREF_32") (pintype "passive"))
    )
    (net (code "176") (name "unconnected-(DD7-XTAL2-Pad12)") (class "Default")
      (node (ref "DD7") (pin "12") (pinfunction "XTAL2_12") (pintype "bidirectional"))
    )
    (net (code "177") (name "unconnected-(DD9-IOA0-Pad21)") (class "Default")
      (node (ref "DD9") (pin "21") (pinfunction "IOA0_21") (pintype "bidirectional"))
    )
    (net (code "178") (name "unconnected-(DD9-IOA1-Pad20)") (class "Default")
      (node (ref "DD9") (pin "20") (pinfunction "IOA1_20") (pintype "bidirectional"))
    )
    (net (code "179") (name "unconnected-(DD9-IOA2-Pad19)") (class "Default")
      (node (ref "DD9") (pin "19") (pinfunction "IOA2_19") (pintype "bidirectional"))
    )
    (net (code "180") (name "unconnected-(DD9-IOA3-Pad18)") (class "Default")
      (node (ref "DD9") (pin "18") (pinfunction "IOA3_18") (pintype "bidirectional"))
    )
    (net (code "181") (name "unconnected-(DD9-IOA4-Pad17)") (class "Default")
      (node (ref "DD9") (pin "17") (pinfunction "IOA4_17") (pintype "bidirectional"))
    )
    (net (code "182") (name "unconnected-(DD9-IOA5-Pad16)") (class "Default")
      (node (ref "DD9") (pin "16") (pinfunction "IOA5_16") (pintype "bidirectional"))
    )
    (net (code "183") (name "unconnected-(DD9-IOA6-Pad15)") (class "Default")
      (node (ref "DD9") (pin "15") (pinfunction "IOA6_15") (pintype "bidirectional"))
    )
    (net (code "184") (name "unconnected-(DD9-IOA7-Pad14)") (class "Default")
      (node (ref "DD9") (pin "14") (pinfunction "IOA7_14") (pintype "bidirectional"))
    )
    (net (code "185") (name "unconnected-(DD9-IOB0-Pad13)") (class "Default")
      (node (ref "DD9") (pin "13") (pinfunction "IOB0_13") (pintype "bidirectional"))
    )
    (net (code "186") (name "unconnected-(DD9-IOB1-Pad12)") (class "Default")
      (node (ref "DD9") (pin "12") (pinfunction "IOB1_12") (pintype "bidirectional"))
    )
    (net (code "187") (name "unconnected-(DD9-IOB2-Pad11)") (class "Default")
      (node (ref "DD9") (pin "11") (pinfunction "IOB2_11") (pintype "bidirectional"))
    )
    (net (code "188") (name "unconnected-(DD9-IOB3-Pad10)") (class "Default")
      (node (ref "DD9") (pin "10") (pinfunction "IOB3_10") (pintype "bidirectional"))
    )
    (net (code "189") (name "unconnected-(DD9-IOB4-Pad9)") (class "Default")
      (node (ref "DD9") (pin "9") (pinfunction "IOB4_9") (pintype "bidirectional"))
    )
    (net (code "190") (name "unconnected-(DD9-IOB5-Pad8)") (class "Default")
      (node (ref "DD9") (pin "8") (pinfunction "IOB5_8") (pintype "bidirectional"))
    )
    (net (code "191") (name "unconnected-(DD9-IOB6-Pad7)") (class "Default")
      (node (ref "DD9") (pin "7") (pinfunction "IOB6_7") (pintype "bidirectional"))
    )
    (net (code "192") (name "unconnected-(DD9-IOB7-Pad6)") (class "Default")
      (node (ref "DD9") (pin "6") (pinfunction "IOB7_6") (pintype "bidirectional"))
    )
    (net (code "193") (name "unconnected-(DD9-MOD-Pad26)") (class "Default")
      (node (ref "DD9") (pin "26") (pinfunction "MOD_26") (pintype "bidirectional"))
    )
    (net (code "194") (name "unconnected-(DD9-TEST1-Pad39)") (class "Default")
      (node (ref "DD9") (pin "39") (pinfunction "TEST1_39") (pintype "bidirectional"))
    )
    (net (code "195") (name "unconnected-(DD12A-Q-Pad5)") (class "Default")
      (node (ref "DD12") (pin "5") (pinfunction "Q_5") (pintype "output"))
    )
    (net (code "196") (name "unconnected-(DD12A-~{Q}-Pad6)") (class "Default")
      (node (ref "DD12") (pin "6") (pinfunction "~{Q}_6") (pintype "output"))
    )
    (net (code "197") (name "unconnected-(X2-Pad2)") (class "Default")
      (node (ref "X2") (pin "2") (pinfunction "2_2") (pintype "passive"))
    )
    (net (code "198") (name "unconnected-(X2-Pad6)") (class "Default")
      (node (ref "X2") (pin "6") (pinfunction "6_6") (pintype "passive"))
    )
    (net (code "199") (name "unconnected-(X2-Pad8)") (class "Default")
      (node (ref "X2") (pin "8") (pinfunction "8_8") (pintype "passive"))
    )
    (net (code "200") (name "unconnected-(X2-Pad10)") (class "Default")
      (node (ref "X2") (pin "10") (pinfunction "10_10") (pintype "passive"))
    )
    (net (code "201") (name "unconnected-(X2-Pad12)") (class "Default")
      (node (ref "X2") (pin "12") (pinfunction "12_12") (pintype "passive"))
    )
    (net (code "202") (name "unconnected-(X2-Pad16)") (class "Default")
      (node (ref "X2") (pin "16") (pinfunction "16_16") (pintype "passive"))
    )
    (net (code "203") (name "unconnected-(X2-Pad20)") (class "Default")
      (node (ref "X2") (pin "20") (pinfunction "20_20") (pintype "passive"))
    )
    (net (code "204") (name "unconnected-(X3-Pad2)") (class "Default")
      (node (ref "X3") (pin "2") (pinfunction "2_2") (pintype "passive"))
    )
    (net (code "205") (name "unconnected-(X3-Pad6)") (class "Default")
      (node (ref "X3") (pin "6") (pinfunction "6_6") (pintype "passive"))
    )
    (net (code "206") (name "unconnected-(X4-CDI#-Pad10)") (class "Default")
      (node (ref "X4") (pin "10") (pinfunction "CDI#_10") (pintype "output"))
    )
    (net (code "207") (name "unconnected-(X4-DAT1-Pad8)") (class "Default")
      (node (ref "X4") (pin "8") (pinfunction "DAT1_8") (pintype "bidirectional"))
    )
    (net (code "208") (name "unconnected-(X4-DAT2-Pad9)") (class "Default")
      (node (ref "X4") (pin "9") (pinfunction "DAT2_9") (pintype "bidirectional"))
    )
    (net (code "209") (name "unconnected-(X4-WP-Pad11)") (class "Default")
      (node (ref "X4") (pin "11") (pinfunction "WP_11") (pintype "output"))
    )
    (net (code "210") (name "unconnected-(X5-Pad7)") (class "Default")
      (node (ref "X5") (pin "7") (pinfunction "7_7") (pintype "passive"))
    )
    (net (code "211") (name "unconnected-(X5-Pad8)") (class "Default")
      (node (ref "X5") (pin "8") (pinfunction "8_8") (pintype "passive"))
    )
  )
)
